# FR4_6_0.net
KiCad netlist of a schematic drawn in EAGLE
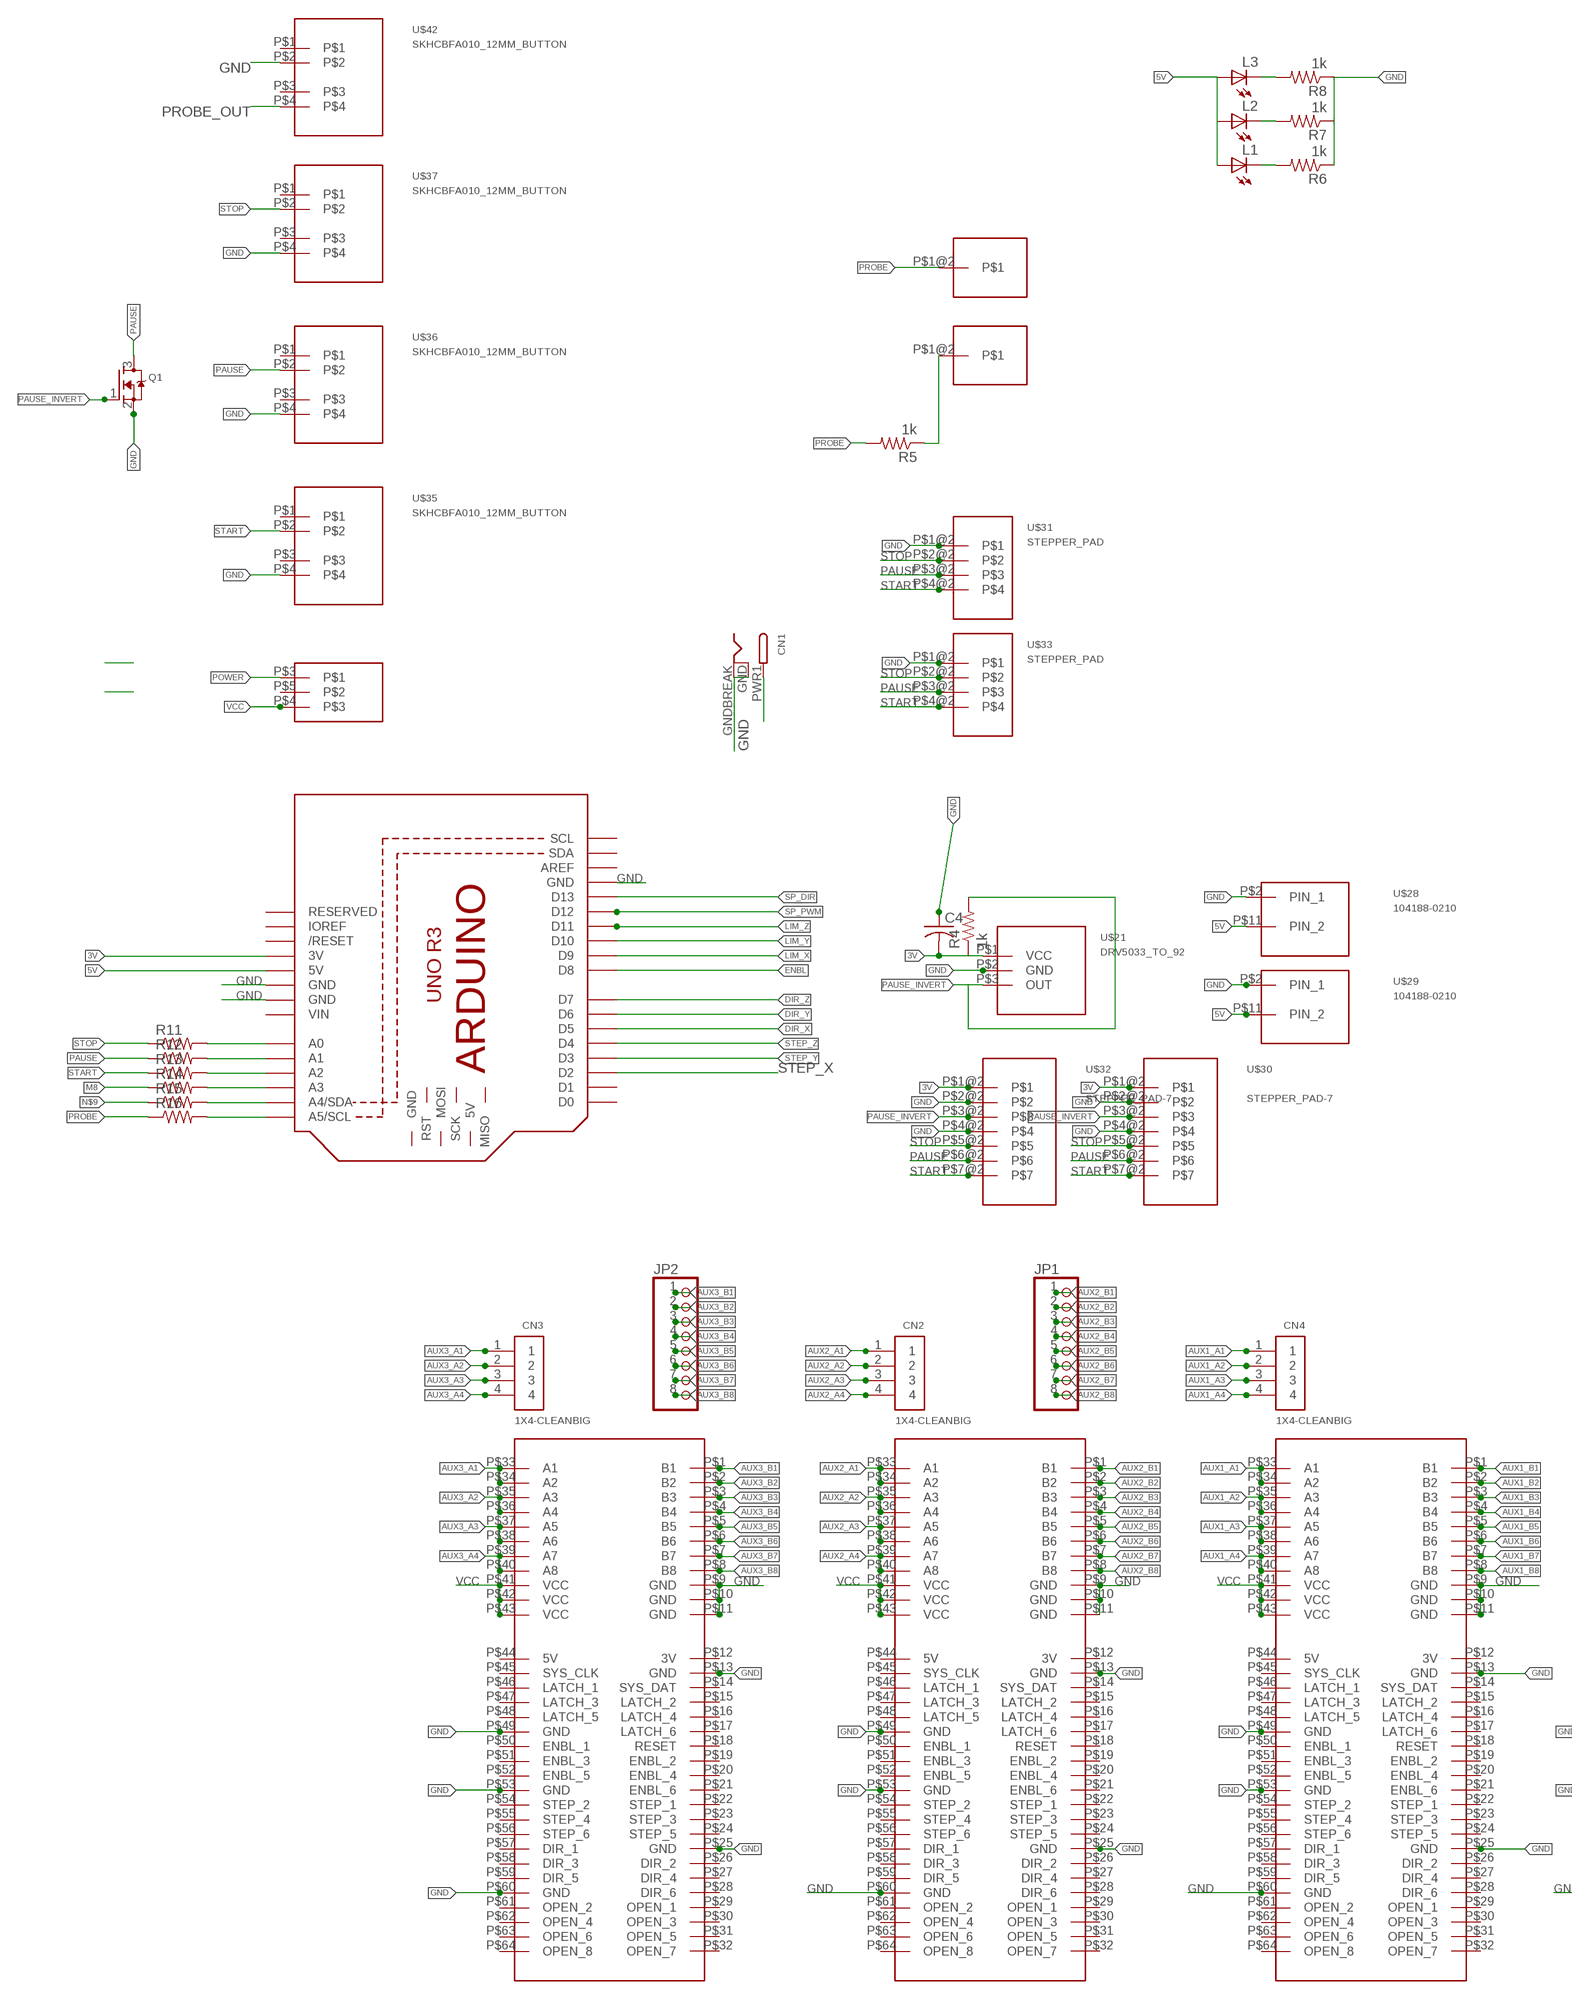
[diagram p0: schematic, sheet 1, part 1 of 2]
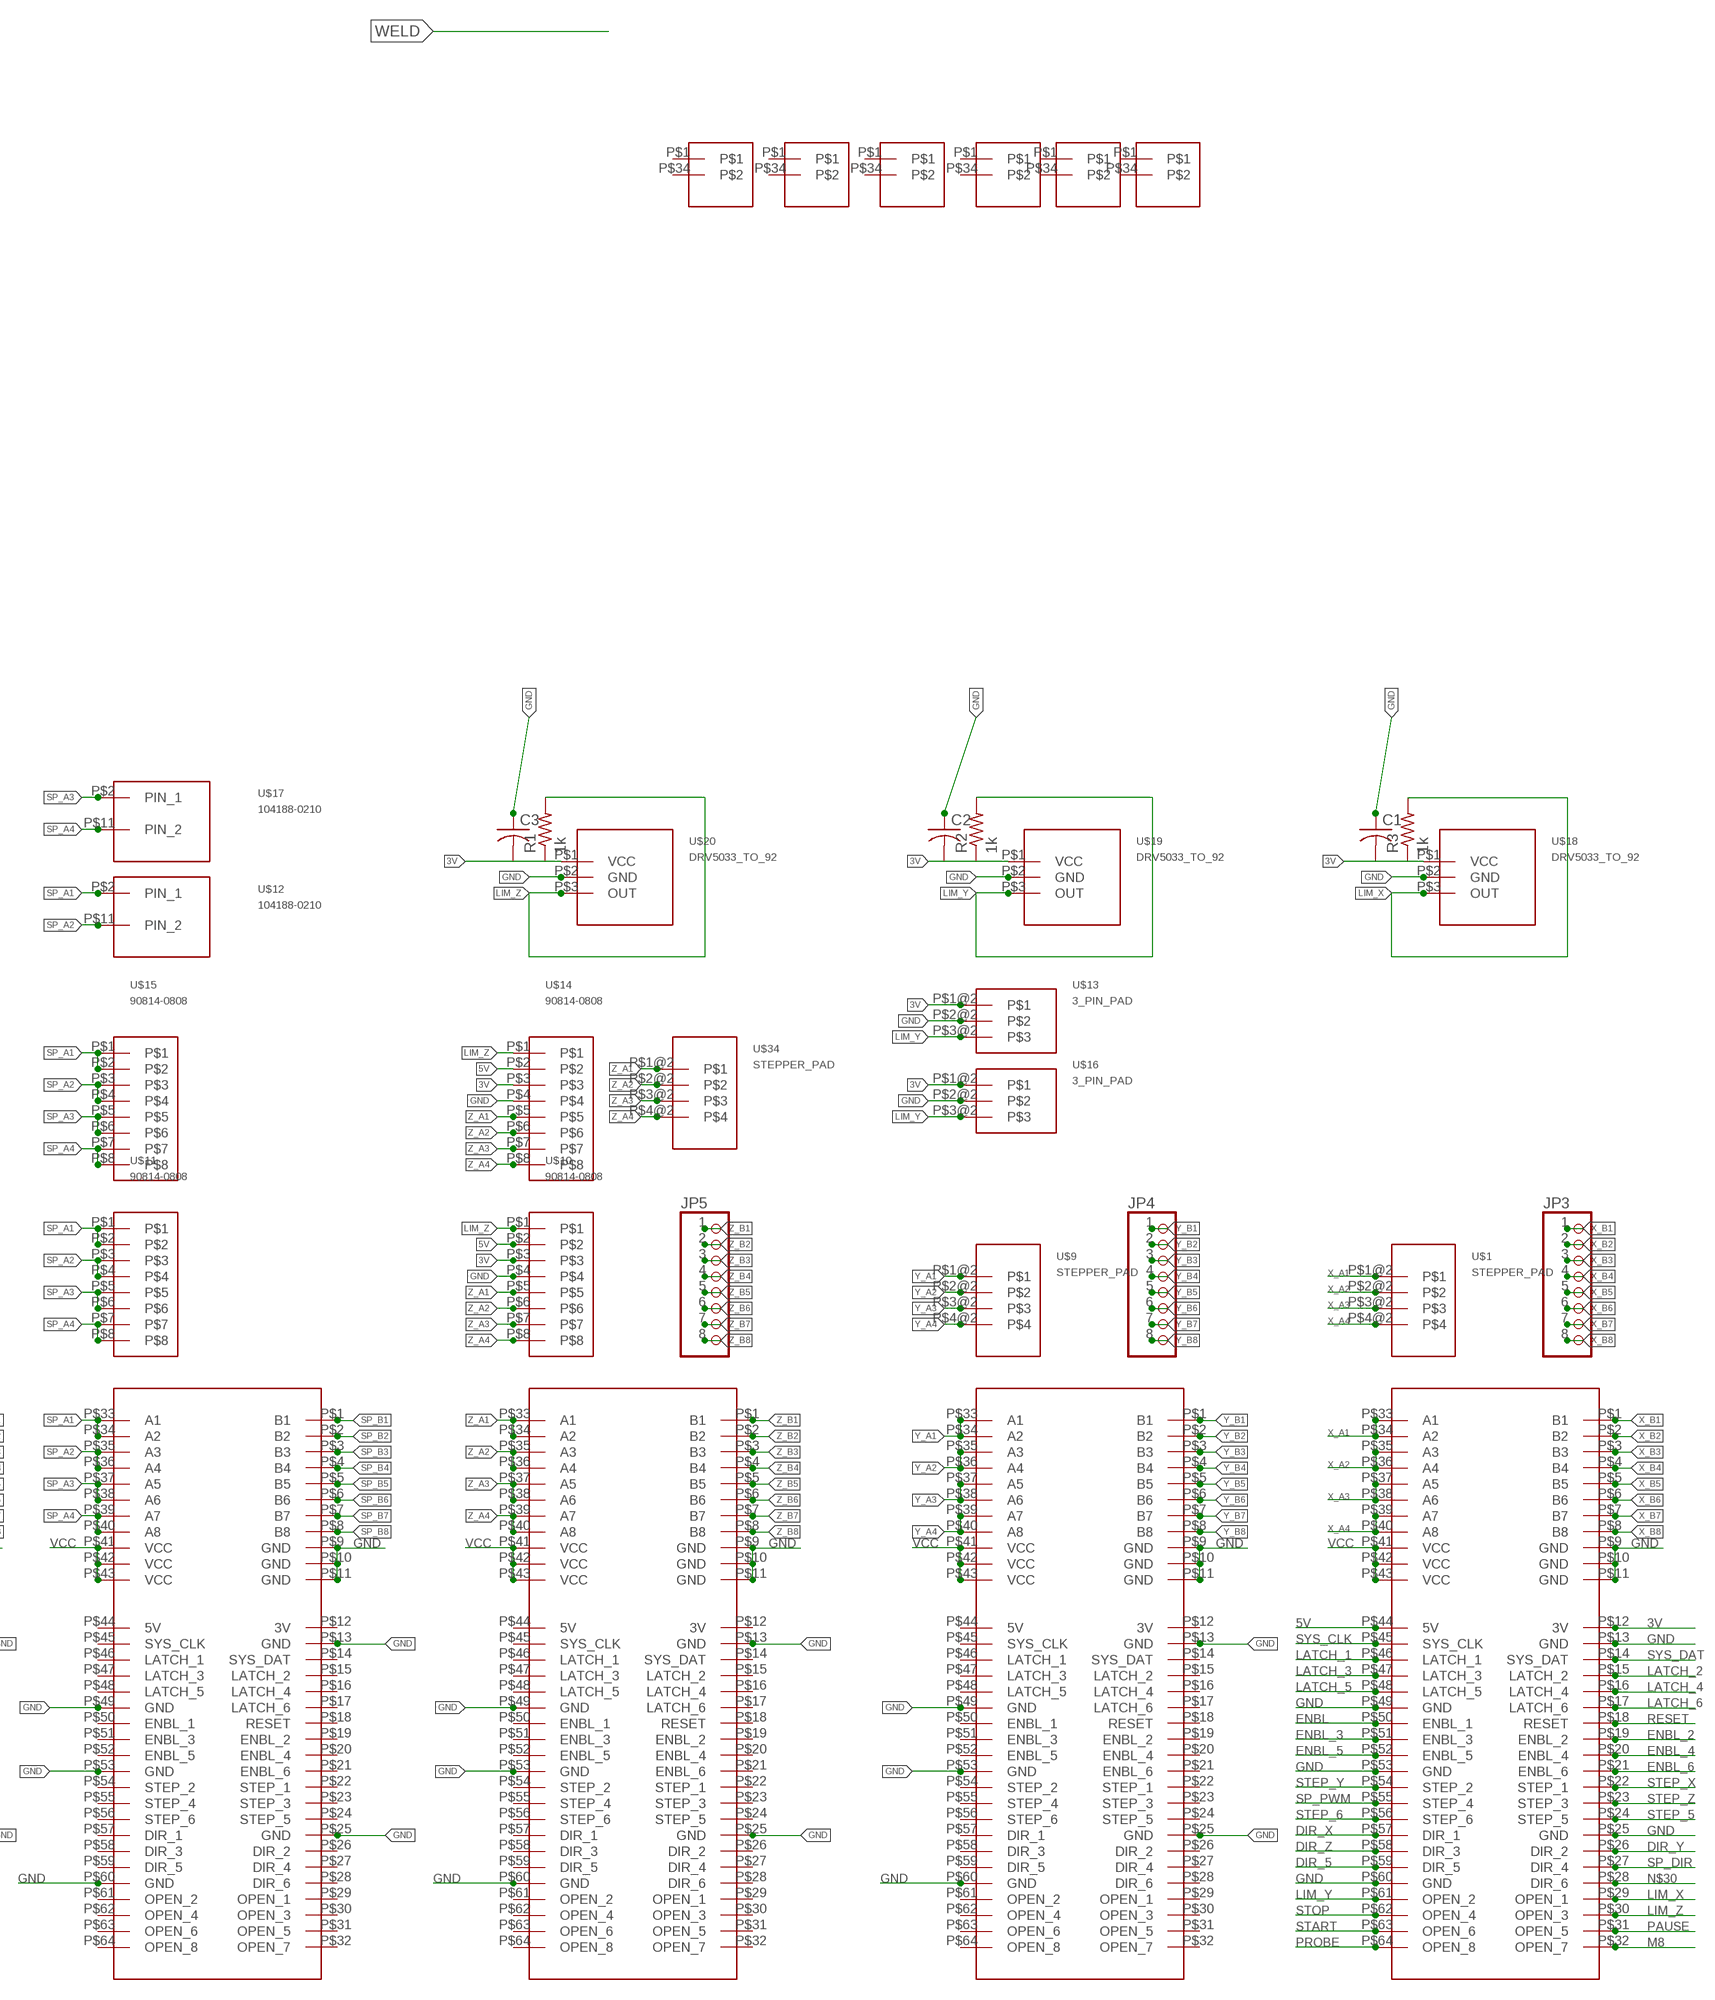
[diagram p1: schematic, sheet 1, part 2 of 2]

(export (version "E")
  (design (tool "Eeschema 10.0.6"))
  (components
    (comp (ref "C1")
      (value "C-USC1210")
      (footprint "eagle-import:C1210")
      (libsource (lib "eagle-import") (part "C-USC1210"))
    )
    (comp (ref "C2")
      (value "C-USC1210")
      (footprint "eagle-import:C1210")
      (libsource (lib "eagle-import") (part "C-USC1210"))
    )
    (comp (ref "C3")
      (value "C-USC1210")
      (footprint "eagle-import:C1210")
      (libsource (lib "eagle-import") (part "C-USC1210"))
    )
    (comp (ref "C4")
      (value "C-USC1210")
      (footprint "eagle-import:C1210")
      (libsource (lib "eagle-import") (part "C-USC1210"))
    )
    (comp (ref "CN1")
      (value "DCBARRELSMT")
      (footprint "eagle-import:DCJACK_2MM_SMT")
      (libsource (lib "eagle-import") (part "DCBARRELSMT"))
    )
    (comp (ref "CN2")
      (value "1X4-CLEANBIG")
      (footprint "eagle-import:1X04-CLEANBIG")
      (libsource (lib "eagle-import") (part "1X4-CLEANBIG"))
    )
    (comp (ref "CN3")
      (value "1X4-CLEANBIG")
      (footprint "eagle-import:1X04-CLEANBIG")
      (libsource (lib "eagle-import") (part "1X4-CLEANBIG"))
    )
    (comp (ref "CN4")
      (value "1X4-CLEANBIG")
      (footprint "eagle-import:1X04-CLEANBIG")
      (libsource (lib "eagle-import") (part "1X4-CLEANBIG"))
    )
    (comp (ref "JP1")
      (value "PINHD-1X8CLEANBIG")
      (footprint "eagle-import:1X08-CLEANBIG")
      (libsource (lib "eagle-import") (part "PINHD-1X8CLEANBIG"))
    )
    (comp (ref "JP2")
      (value "PINHD-1X8CLEANBIG")
      (footprint "eagle-import:1X08-CLEANBIG")
      (libsource (lib "eagle-import") (part "PINHD-1X8CLEANBIG"))
    )
    (comp (ref "JP3")
      (value "PINHD-1X8CLEANBIG")
      (footprint "eagle-import:1X08-CLEANBIG")
      (libsource (lib "eagle-import") (part "PINHD-1X8CLEANBIG"))
    )
    (comp (ref "JP4")
      (value "PINHD-1X8CLEANBIG")
      (footprint "eagle-import:1X08-CLEANBIG")
      (libsource (lib "eagle-import") (part "PINHD-1X8CLEANBIG"))
    )
    (comp (ref "JP5")
      (value "PINHD-1X8CLEANBIG")
      (footprint "eagle-import:1X08-CLEANBIG")
      (libsource (lib "eagle-import") (part "PINHD-1X8CLEANBIG"))
    )
    (comp (ref "L1")
      (value "LEDCHIPLED_1206")
      (footprint "eagle-import:CHIPLED_1206")
      (libsource (lib "eagle-import") (part "LEDCHIPLED_1206"))
    )
    (comp (ref "L2")
      (value "LEDCHIPLED_1206")
      (footprint "eagle-import:CHIPLED_1206")
      (libsource (lib "eagle-import") (part "LEDCHIPLED_1206"))
    )
    (comp (ref "L3")
      (value "LEDCHIPLED_1206")
      (footprint "eagle-import:CHIPLED_1206")
      (libsource (lib "eagle-import") (part "LEDCHIPLED_1206"))
    )
    (comp (ref "M1")
      (value "ARDUINO_R3_ICSP")
      (footprint "eagle-import:ARDUINOR3_ICSP")
      (libsource (lib "eagle-import") (part "ARDUINO_R3_ICSP"))
    )
    (comp (ref "Q1")
      (value "MOSFET-NREFLOW")
      (footprint "eagle-import:SOT23")
      (libsource (lib "eagle-import") (part "MOSFET-NREFLOW"))
    )
    (comp (ref "R1")
      (value "1k")
      (footprint "eagle-import:R1210")
      (libsource (lib "eagle-import") (part "R-US_R1210"))
    )
    (comp (ref "R2")
      (value "1k")
      (footprint "eagle-import:R1210")
      (libsource (lib "eagle-import") (part "R-US_R1210"))
    )
    (comp (ref "R3")
      (value "1k")
      (footprint "eagle-import:R1210")
      (libsource (lib "eagle-import") (part "R-US_R1210"))
    )
    (comp (ref "R4")
      (value "1k")
      (footprint "eagle-import:R1210")
      (libsource (lib "eagle-import") (part "R-US_R1210"))
    )
    (comp (ref "R5")
      (value "1k")
      (footprint "eagle-import:R1210")
      (libsource (lib "eagle-import") (part "R-US_R1210"))
    )
    (comp (ref "R6")
      (value "1k")
      (footprint "eagle-import:R1210")
      (libsource (lib "eagle-import") (part "R-US_R1210"))
    )
    (comp (ref "R7")
      (value "1k")
      (footprint "eagle-import:R1210")
      (libsource (lib "eagle-import") (part "R-US_R1210"))
    )
    (comp (ref "R8")
      (value "1k")
      (footprint "eagle-import:R1210")
      (libsource (lib "eagle-import") (part "R-US_R1210"))
    )
    (comp (ref "R11")
      (value "R-US_R1206")
      (footprint "eagle-import:R1206")
      (libsource (lib "eagle-import") (part "R-US_R1206"))
    )
    (comp (ref "R12")
      (value "R-US_R1206")
      (footprint "eagle-import:R1206")
      (libsource (lib "eagle-import") (part "R-US_R1206"))
    )
    (comp (ref "R13")
      (value "R-US_R1206")
      (footprint "eagle-import:R1206")
      (libsource (lib "eagle-import") (part "R-US_R1206"))
    )
    (comp (ref "R14")
      (value "R-US_R1206")
      (footprint "eagle-import:R1206")
      (libsource (lib "eagle-import") (part "R-US_R1206"))
    )
    (comp (ref "R15")
      (value "R-US_R1206")
      (footprint "eagle-import:R1206")
      (libsource (lib "eagle-import") (part "R-US_R1206"))
    )
    (comp (ref "R16")
      (value "R-US_R1206")
      (footprint "eagle-import:R1206")
      (libsource (lib "eagle-import") (part "R-US_R1206"))
    )
    (comp (ref "U$1")
      (value "STEPPER_PAD")
      (footprint "eagle-import:STEPPER_PAD")
      (libsource (lib "eagle-import") (part "STEPPER_PAD"))
    )
    (comp (ref "U$2")
      (value "10018784-10211TLF-TRACE")
      (footprint "eagle-import:10018784-10211TLF-TRACE")
      (libsource (lib "eagle-import") (part "10018784-10211TLF-TRACE"))
    )
    (comp (ref "U$3")
      (value "10018784-10211TLF-TRACE")
      (footprint "eagle-import:10018784-10211TLF-TRACE")
      (libsource (lib "eagle-import") (part "10018784-10211TLF-TRACE"))
    )
    (comp (ref "U$4")
      (value "10018784-10211TLF-TRACE")
      (footprint "eagle-import:10018784-10211TLF-TRACE")
      (libsource (lib "eagle-import") (part "10018784-10211TLF-TRACE"))
    )
    (comp (ref "U$5")
      (value "10018784-10211TLF-TRACE")
      (footprint "eagle-import:10018784-10211TLF-TRACE")
      (libsource (lib "eagle-import") (part "10018784-10211TLF-TRACE"))
    )
    (comp (ref "U$6")
      (value "10018784-10211TLF-TRACE")
      (footprint "eagle-import:10018784-10211TLF-TRACE")
      (libsource (lib "eagle-import") (part "10018784-10211TLF-TRACE"))
    )
    (comp (ref "U$7")
      (value "10018784-10211TLF-TRACE")
      (footprint "eagle-import:10018784-10211TLF-TRACE")
      (libsource (lib "eagle-import") (part "10018784-10211TLF-TRACE"))
    )
    (comp (ref "U$8")
      (value "10018784-10211TLF-")
      (footprint "eagle-import:1001874-10211TLF-")
      (libsource (lib "eagle-import") (part "10018784-10211TLF-"))
    )
    (comp (ref "U$9")
      (value "STEPPER_PAD")
      (footprint "eagle-import:STEPPER_PAD")
      (libsource (lib "eagle-import") (part "STEPPER_PAD"))
    )
    (comp (ref "U$10")
      (value "90814-0808")
      (footprint "eagle-import:90814-0808")
      (libsource (lib "eagle-import") (part "90814-0808"))
    )
    (comp (ref "U$11")
      (value "90814-0808")
      (footprint "eagle-import:90814-0808")
      (libsource (lib "eagle-import") (part "90814-0808"))
    )
    (comp (ref "U$12")
      (value "104188-0210")
      (footprint "eagle-import:104188-0210")
      (libsource (lib "eagle-import") (part "104188-0210"))
    )
    (comp (ref "U$13")
      (value "3_PIN_PAD")
      (footprint "eagle-import:3_WIRE_PAD")
      (libsource (lib "eagle-import") (part "3_PIN_PAD"))
    )
    (comp (ref "U$14")
      (value "90814-0808")
      (footprint "eagle-import:90814-0808")
      (libsource (lib "eagle-import") (part "90814-0808"))
    )
    (comp (ref "U$15")
      (value "90814-0808")
      (footprint "eagle-import:90814-0808")
      (libsource (lib "eagle-import") (part "90814-0808"))
    )
    (comp (ref "U$16")
      (value "3_PIN_PAD")
      (footprint "eagle-import:3_WIRE_PAD")
      (libsource (lib "eagle-import") (part "3_PIN_PAD"))
    )
    (comp (ref "U$17")
      (value "104188-0210")
      (footprint "eagle-import:104188-0210")
      (libsource (lib "eagle-import") (part "104188-0210"))
    )
    (comp (ref "U$18")
      (value "DRV5033_TO_92")
      (footprint "eagle-import:DRV5033_TO_92")
      (libsource (lib "eagle-import") (part "DRV5033_TO_92"))
    )
    (comp (ref "U$19")
      (value "DRV5033_TO_92")
      (footprint "eagle-import:DRV5033_TO_92")
      (libsource (lib "eagle-import") (part "DRV5033_TO_92"))
    )
    (comp (ref "U$20")
      (value "DRV5033_TO_92")
      (footprint "eagle-import:DRV5033_TO_92")
      (libsource (lib "eagle-import") (part "DRV5033_TO_92"))
    )
    (comp (ref "U$21")
      (value "DRV5033_TO_92")
      (footprint "eagle-import:DRV5033_TO_92")
      (libsource (lib "eagle-import") (part "DRV5033_TO_92"))
    )
    (comp (ref "U$22")
      (value "WELDPAD_.79X.353")
      (footprint "eagle-import:WELDPAD_.79X.353")
      (libsource (lib "eagle-import") (part "WELDPAD_.79X.353"))
    )
    (comp (ref "U$23")
      (value "WELDPAD_.79X.353")
      (footprint "eagle-import:WELDPAD_.79X.353")
      (libsource (lib "eagle-import") (part "WELDPAD_.79X.353"))
    )
    (comp (ref "U$24")
      (value "WELDPAD_.79X.353")
      (footprint "eagle-import:WELDPAD_.79X.353")
      (libsource (lib "eagle-import") (part "WELDPAD_.79X.353"))
    )
    (comp (ref "U$25")
      (value "WELDPAD_.79X.353")
      (footprint "eagle-import:WELDPAD_.79X.353")
      (libsource (lib "eagle-import") (part "WELDPAD_.79X.353"))
    )
    (comp (ref "U$26")
      (value "WELDPAD_.79X.353")
      (footprint "eagle-import:WELDPAD_.79X.353")
      (libsource (lib "eagle-import") (part "WELDPAD_.79X.353"))
    )
    (comp (ref "U$27")
      (value "WELDPAD_.79X.353")
      (footprint "eagle-import:WELDPAD_.79X.353")
      (libsource (lib "eagle-import") (part "WELDPAD_.79X.353"))
    )
    (comp (ref "U$28")
      (value "104188-0210")
      (footprint "eagle-import:104188-0210")
      (libsource (lib "eagle-import") (part "104188-0210"))
    )
    (comp (ref "U$29")
      (value "104188-0210")
      (footprint "eagle-import:104188-0210")
      (libsource (lib "eagle-import") (part "104188-0210"))
    )
    (comp (ref "U$30")
      (value "STEPPER_PAD-7")
      (footprint "eagle-import:STEPPER_PAD-7")
      (libsource (lib "eagle-import") (part "STEPPER_PAD-7"))
    )
    (comp (ref "U$31")
      (value "STEPPER_PAD")
      (footprint "eagle-import:STEPPER_PAD")
      (libsource (lib "eagle-import") (part "STEPPER_PAD"))
    )
    (comp (ref "U$32")
      (value "STEPPER_PAD-7")
      (footprint "eagle-import:STEPPER_PAD-7")
      (libsource (lib "eagle-import") (part "STEPPER_PAD-7"))
    )
    (comp (ref "U$33")
      (value "STEPPER_PAD")
      (footprint "eagle-import:STEPPER_PAD")
      (libsource (lib "eagle-import") (part "STEPPER_PAD"))
    )
    (comp (ref "U$34")
      (value "STEPPER_PAD")
      (footprint "eagle-import:STEPPER_PAD")
      (libsource (lib "eagle-import") (part "STEPPER_PAD"))
    )
    (comp (ref "U$35")
      (value "SKHCBFA010_12MM_BUTTON")
      (footprint "eagle-import:12MM_BUTTON")
      (libsource (lib "eagle-import") (part "SKHCBFA010_12MM_BUTTON"))
    )
    (comp (ref "U$36")
      (value "SKHCBFA010_12MM_BUTTON")
      (footprint "eagle-import:12MM_BUTTON")
      (libsource (lib "eagle-import") (part "SKHCBFA010_12MM_BUTTON"))
    )
    (comp (ref "U$37")
      (value "SKHCBFA010_12MM_BUTTON")
      (footprint "eagle-import:12MM_BUTTON")
      (libsource (lib "eagle-import") (part "SKHCBFA010_12MM_BUTTON"))
    )
    (comp (ref "U$39")
      (value "1PIN_PAD")
      (footprint "eagle-import:1PIN_PAD")
      (libsource (lib "eagle-import") (part "1PIN_PAD"))
    )
    (comp (ref "U$40")
      (value "1PIN_PAD")
      (footprint "eagle-import:1PIN_PAD")
      (libsource (lib "eagle-import") (part "1PIN_PAD"))
    )
    (comp (ref "U$41")
      (value "100SP1T2B4M6QE")
      (footprint "eagle-import:100SP1T2B4M6QE")
      (libsource (lib "eagle-import") (part "100SP1T2B4M6QE"))
    )
    (comp (ref "U$42")
      (value "SKHCBFA010_12MM_BUTTON")
      (footprint "eagle-import:12MM_BUTTON")
      (libsource (lib "eagle-import") (part "SKHCBFA010_12MM_BUTTON"))
    )
  )
  (nets
    (net (code "1") (name "/DIR_5") (class "Default")
      (node (ref "U$8") (pin "P$59") (pinfunction "DIR_5_P$59") (pintype "bidirectional"))
    )
    (net (code "2") (name "/ENBL_2") (class "Default")
      (node (ref "U$8") (pin "P$19") (pinfunction "ENBL_2_P$19") (pintype "bidirectional"))
    )
    (net (code "3") (name "/ENBL_3") (class "Default")
      (node (ref "U$8") (pin "P$51") (pinfunction "ENBL_3_P$51") (pintype "bidirectional"))
    )
    (net (code "4") (name "/ENBL_4") (class "Default")
      (node (ref "U$8") (pin "P$20") (pinfunction "ENBL_4_P$20") (pintype "bidirectional"))
    )
    (net (code "5") (name "/ENBL_5") (class "Default")
      (node (ref "U$8") (pin "P$52") (pinfunction "ENBL_5_P$52") (pintype "bidirectional"))
    )
    (net (code "6") (name "/ENBL_6") (class "Default")
      (node (ref "U$8") (pin "P$21") (pinfunction "ENBL_6_P$21") (pintype "bidirectional"))
    )
    (net (code "7") (name "/LATCH_1") (class "Default")
      (node (ref "U$8") (pin "P$46") (pinfunction "LATCH_1_P$46") (pintype "bidirectional"))
    )
    (net (code "8") (name "/LATCH_2") (class "Default")
      (node (ref "U$8") (pin "P$15") (pinfunction "LATCH_2_P$15") (pintype "bidirectional"))
    )
    (net (code "9") (name "/LATCH_3") (class "Default")
      (node (ref "U$8") (pin "P$47") (pinfunction "LATCH_3_P$47") (pintype "bidirectional"))
    )
    (net (code "10") (name "/LATCH_4") (class "Default")
      (node (ref "U$8") (pin "P$16") (pinfunction "LATCH_4_P$16") (pintype "bidirectional"))
    )
    (net (code "11") (name "/LATCH_5") (class "Default")
      (node (ref "U$8") (pin "P$48") (pinfunction "LATCH_5_P$48") (pintype "bidirectional"))
    )
    (net (code "12") (name "/LATCH_6") (class "Default")
      (node (ref "U$8") (pin "P$17") (pinfunction "LATCH_6_P$17") (pintype "bidirectional"))
    )
    (net (code "13") (name "/N$30") (class "Default")
      (node (ref "U$8") (pin "P$28") (pinfunction "DIR_6_P$28") (pintype "bidirectional"))
    )
    (net (code "14") (name "/PROBE_OUT") (class "Default")
      (node (ref "R5") (pin "1") (pinfunction "1_1") (pintype "passive"))
      (node (ref "U$39") (pin "P$1@2") (pinfunction "P$1_P$1@2") (pintype "bidirectional"))
      (node (ref "U$42") (pin "P$4") (pinfunction "P$4_P$4") (pintype "bidirectional"))
    )
    (net (code "15") (name "/RESET") (class "Default")
      (node (ref "U$8") (pin "P$18") (pinfunction "RESET_P$18") (pintype "bidirectional"))
    )
    (net (code "16") (name "/STEP_5") (class "Default")
      (node (ref "U$8") (pin "P$24") (pinfunction "STEP_5_P$24") (pintype "bidirectional"))
    )
    (net (code "17") (name "/STEP_6") (class "Default")
      (node (ref "U$8") (pin "P$56") (pinfunction "STEP_6_P$56") (pintype "bidirectional"))
    )
    (net (code "18") (name "/STEP_X") (class "Default")
      (node (ref "M1") (pin "D2") (pinfunction "D2_D2") (pintype "bidirectional"))
      (node (ref "U$8") (pin "P$22") (pinfunction "STEP_1_P$22") (pintype "bidirectional"))
    )
    (net (code "19") (name "/SYS_CLK") (class "Default")
      (node (ref "U$8") (pin "P$45") (pinfunction "SYS_CLK_P$45") (pintype "bidirectional"))
    )
    (net (code "20") (name "/SYS_DAT") (class "Default")
      (node (ref "U$8") (pin "P$14") (pinfunction "SYS_DAT_P$14") (pintype "bidirectional"))
    )
    (net (code "21") (name "/VIN") (class "Default")
      (node (ref "M1") (pin "VIN") (pinfunction "VIN_VIN") (pintype "power_in"))
    )
    (net (code "22") (name "/X_A1") (class "Default")
      (node (ref "U$1") (pin "P$1@2") (pinfunction "P$1_P$1@2") (pintype "bidirectional"))
      (node (ref "U$8") (pin "P$33") (pinfunction "A1_P$33") (pintype "bidirectional"))
      (node (ref "U$8") (pin "P$34") (pinfunction "A2_P$34") (pintype "bidirectional"))
    )
    (net (code "23") (name "/X_A2") (class "Default")
      (node (ref "U$1") (pin "P$2@2") (pinfunction "P$2_P$2@2") (pintype "bidirectional"))
      (node (ref "U$8") (pin "P$35") (pinfunction "A3_P$35") (pintype "bidirectional"))
      (node (ref "U$8") (pin "P$36") (pinfunction "A4_P$36") (pintype "bidirectional"))
    )
    (net (code "24") (name "/X_A3") (class "Default")
      (node (ref "U$1") (pin "P$3@2") (pinfunction "P$3_P$3@2") (pintype "bidirectional"))
      (node (ref "U$8") (pin "P$37") (pinfunction "A5_P$37") (pintype "bidirectional"))
      (node (ref "U$8") (pin "P$38") (pinfunction "A6_P$38") (pintype "bidirectional"))
    )
    (net (code "25") (name "/X_A4") (class "Default")
      (node (ref "U$1") (pin "P$4@2") (pinfunction "P$4_P$4@2") (pintype "bidirectional"))
      (node (ref "U$8") (pin "P$39") (pinfunction "A7_P$39") (pintype "bidirectional"))
      (node (ref "U$8") (pin "P$40") (pinfunction "A8_P$40") (pintype "bidirectional"))
    )
    (net (code "26") (name "3V") (class "Default")
      (node (ref "C1") (pin "2") (pinfunction "2_2") (pintype "passive"))
      (node (ref "C2") (pin "2") (pinfunction "2_2") (pintype "passive"))
      (node (ref "C3") (pin "2") (pinfunction "2_2") (pintype "passive"))
      (node (ref "C4") (pin "2") (pinfunction "2_2") (pintype "passive"))
      (node (ref "M1") (pin "3V") (pinfunction "3V_3V") (pintype "power_in"))
      (node (ref "R1") (pin "1") (pinfunction "1_1") (pintype "passive"))
      (node (ref "R2") (pin "1") (pinfunction "1_1") (pintype "passive"))
      (node (ref "R3") (pin "1") (pinfunction "1_1") (pintype "passive"))
      (node (ref "R4") (pin "1") (pinfunction "1_1") (pintype "passive"))
      (node (ref "U$10") (pin "P$3") (pinfunction "P$3_P$3") (pintype "bidirectional"))
      (node (ref "U$13") (pin "P$1@2") (pinfunction "P$1_P$1@2") (pintype "bidirectional"))
      (node (ref "U$14") (pin "P$3") (pinfunction "P$3_P$3") (pintype "bidirectional"))
      (node (ref "U$16") (pin "P$1@2") (pinfunction "P$1_P$1@2") (pintype "bidirectional"))
      (node (ref "U$18") (pin "P$1") (pinfunction "VCC_P$1") (pintype "bidirectional"))
      (node (ref "U$19") (pin "P$1") (pinfunction "VCC_P$1") (pintype "bidirectional"))
      (node (ref "U$20") (pin "P$1") (pinfunction "VCC_P$1") (pintype "bidirectional"))
      (node (ref "U$21") (pin "P$1") (pinfunction "VCC_P$1") (pintype "bidirectional"))
      (node (ref "U$30") (pin "P$1@2") (pinfunction "P$1_P$1@2") (pintype "bidirectional"))
      (node (ref "U$32") (pin "P$1@2") (pinfunction "P$1_P$1@2") (pintype "bidirectional"))
      (node (ref "U$8") (pin "P$12") (pinfunction "3V_P$12") (pintype "bidirectional"))
    )
    (net (code "27") (name "5V") (class "Default")
      (node (ref "L1") (pin "A") (pinfunction "A_A") (pintype "passive"))
      (node (ref "L2") (pin "A") (pinfunction "A_A") (pintype "passive"))
      (node (ref "L3") (pin "A") (pinfunction "A_A") (pintype "passive"))
      (node (ref "M1") (pin "5V") (pinfunction "5V_5V") (pintype "power_in"))
      (node (ref "U$10") (pin "P$2") (pinfunction "P$2_P$2") (pintype "bidirectional"))
      (node (ref "U$14") (pin "P$2") (pinfunction "P$2_P$2") (pintype "bidirectional"))
      (node (ref "U$28") (pin "P$11") (pinfunction "PIN_2_P$11") (pintype "bidirectional"))
      (node (ref "U$29") (pin "P$11") (pinfunction "PIN_2_P$11") (pintype "bidirectional"))
      (node (ref "U$8") (pin "P$44") (pinfunction "5V_P$44") (pintype "bidirectional"))
    )
    (net (code "28") (name "AUX1_A1") (class "Default")
      (node (ref "CN4") (pin "1") (pinfunction "1_1") (pintype "bidirectional"))
      (node (ref "U$4") (pin "P$33") (pinfunction "A1_P$33") (pintype "bidirectional"))
      (node (ref "U$4") (pin "P$34") (pinfunction "A2_P$34") (pintype "bidirectional"))
    )
    (net (code "29") (name "AUX1_A2") (class "Default")
      (node (ref "CN4") (pin "2") (pinfunction "2_2") (pintype "bidirectional"))
      (node (ref "U$4") (pin "P$35") (pinfunction "A3_P$35") (pintype "bidirectional"))
      (node (ref "U$4") (pin "P$36") (pinfunction "A4_P$36") (pintype "bidirectional"))
    )
    (net (code "30") (name "AUX1_A3") (class "Default")
      (node (ref "CN4") (pin "3") (pinfunction "3_3") (pintype "bidirectional"))
      (node (ref "U$4") (pin "P$37") (pinfunction "A5_P$37") (pintype "bidirectional"))
      (node (ref "U$4") (pin "P$38") (pinfunction "A6_P$38") (pintype "bidirectional"))
    )
    (net (code "31") (name "AUX1_A4") (class "Default")
      (node (ref "CN4") (pin "4") (pinfunction "4_4") (pintype "bidirectional"))
      (node (ref "U$4") (pin "P$39") (pinfunction "A7_P$39") (pintype "bidirectional"))
      (node (ref "U$4") (pin "P$40") (pinfunction "A8_P$40") (pintype "bidirectional"))
    )
    (net (code "32") (name "AUX1_B1") (class "Default")
      (node (ref "U$4") (pin "P$1") (pinfunction "B1_P$1") (pintype "bidirectional"))
    )
    (net (code "33") (name "AUX1_B2") (class "Default")
      (node (ref "U$4") (pin "P$2") (pinfunction "B2_P$2") (pintype "bidirectional"))
    )
    (net (code "34") (name "AUX1_B3") (class "Default")
      (node (ref "U$4") (pin "P$3") (pinfunction "B3_P$3") (pintype "bidirectional"))
    )
    (net (code "35") (name "AUX1_B4") (class "Default")
      (node (ref "U$4") (pin "P$4") (pinfunction "B4_P$4") (pintype "bidirectional"))
    )
    (net (code "36") (name "AUX1_B5") (class "Default")
      (node (ref "U$4") (pin "P$5") (pinfunction "B5_P$5") (pintype "bidirectional"))
    )
    (net (code "37") (name "AUX1_B6") (class "Default")
      (node (ref "U$4") (pin "P$6") (pinfunction "B6_P$6") (pintype "bidirectional"))
    )
    (net (code "38") (name "AUX1_B7") (class "Default")
      (node (ref "U$4") (pin "P$7") (pinfunction "B7_P$7") (pintype "bidirectional"))
    )
    (net (code "39") (name "AUX1_B8") (class "Default")
      (node (ref "U$4") (pin "P$8") (pinfunction "B8_P$8") (pintype "bidirectional"))
    )
    (net (code "40") (name "AUX2_A1") (class "Default")
      (node (ref "CN2") (pin "1") (pinfunction "1_1") (pintype "bidirectional"))
      (node (ref "U$3") (pin "P$33") (pinfunction "A1_P$33") (pintype "bidirectional"))
      (node (ref "U$3") (pin "P$34") (pinfunction "A2_P$34") (pintype "bidirectional"))
    )
    (net (code "41") (name "AUX2_A2") (class "Default")
      (node (ref "CN2") (pin "2") (pinfunction "2_2") (pintype "bidirectional"))
      (node (ref "U$3") (pin "P$35") (pinfunction "A3_P$35") (pintype "bidirectional"))
      (node (ref "U$3") (pin "P$36") (pinfunction "A4_P$36") (pintype "bidirectional"))
    )
    (net (code "42") (name "AUX2_A3") (class "Default")
      (node (ref "CN2") (pin "3") (pinfunction "3_3") (pintype "bidirectional"))
      (node (ref "U$3") (pin "P$37") (pinfunction "A5_P$37") (pintype "bidirectional"))
      (node (ref "U$3") (pin "P$38") (pinfunction "A6_P$38") (pintype "bidirectional"))
    )
    (net (code "43") (name "AUX2_A4") (class "Default")
      (node (ref "CN2") (pin "4") (pinfunction "4_4") (pintype "bidirectional"))
      (node (ref "U$3") (pin "P$39") (pinfunction "A7_P$39") (pintype "bidirectional"))
      (node (ref "U$3") (pin "P$40") (pinfunction "A8_P$40") (pintype "bidirectional"))
    )
    (net (code "44") (name "AUX2_B1") (class "Default")
      (node (ref "JP1") (pin "1") (pinfunction "1_1") (pintype "passive"))
      (node (ref "U$3") (pin "P$1") (pinfunction "B1_P$1") (pintype "bidirectional"))
    )
    (net (code "45") (name "AUX2_B2") (class "Default")
      (node (ref "JP1") (pin "2") (pinfunction "2_2") (pintype "passive"))
      (node (ref "U$3") (pin "P$2") (pinfunction "B2_P$2") (pintype "bidirectional"))
    )
    (net (code "46") (name "AUX2_B3") (class "Default")
      (node (ref "JP1") (pin "3") (pinfunction "3_3") (pintype "passive"))
      (node (ref "U$3") (pin "P$3") (pinfunction "B3_P$3") (pintype "bidirectional"))
    )
    (net (code "47") (name "AUX2_B4") (class "Default")
      (node (ref "JP1") (pin "4") (pinfunction "4_4") (pintype "passive"))
      (node (ref "U$3") (pin "P$4") (pinfunction "B4_P$4") (pintype "bidirectional"))
    )
    (net (code "48") (name "AUX2_B5") (class "Default")
      (node (ref "JP1") (pin "5") (pinfunction "5_5") (pintype "passive"))
      (node (ref "U$3") (pin "P$5") (pinfunction "B5_P$5") (pintype "bidirectional"))
    )
    (net (code "49") (name "AUX2_B6") (class "Default")
      (node (ref "JP1") (pin "6") (pinfunction "6_6") (pintype "passive"))
      (node (ref "U$3") (pin "P$6") (pinfunction "B6_P$6") (pintype "bidirectional"))
    )
    (net (code "50") (name "AUX2_B7") (class "Default")
      (node (ref "JP1") (pin "7") (pinfunction "7_7") (pintype "passive"))
      (node (ref "U$3") (pin "P$7") (pinfunction "B7_P$7") (pintype "bidirectional"))
    )
    (net (code "51") (name "AUX2_B8") (class "Default")
      (node (ref "JP1") (pin "8") (pinfunction "8_8") (pintype "passive"))
      (node (ref "U$3") (pin "P$8") (pinfunction "B8_P$8") (pintype "bidirectional"))
    )
    (net (code "52") (name "AUX3_A1") (class "Default")
      (node (ref "CN3") (pin "1") (pinfunction "1_1") (pintype "bidirectional"))
      (node (ref "U$2") (pin "P$33") (pinfunction "A1_P$33") (pintype "bidirectional"))
      (node (ref "U$2") (pin "P$34") (pinfunction "A2_P$34") (pintype "bidirectional"))
    )
    (net (code "53") (name "AUX3_A2") (class "Default")
      (node (ref "CN3") (pin "2") (pinfunction "2_2") (pintype "bidirectional"))
      (node (ref "U$2") (pin "P$35") (pinfunction "A3_P$35") (pintype "bidirectional"))
      (node (ref "U$2") (pin "P$36") (pinfunction "A4_P$36") (pintype "bidirectional"))
    )
    (net (code "54") (name "AUX3_A3") (class "Default")
      (node (ref "CN3") (pin "3") (pinfunction "3_3") (pintype "bidirectional"))
      (node (ref "U$2") (pin "P$37") (pinfunction "A5_P$37") (pintype "bidirectional"))
      (node (ref "U$2") (pin "P$38") (pinfunction "A6_P$38") (pintype "bidirectional"))
    )
    (net (code "55") (name "AUX3_A4") (class "Default")
      (node (ref "CN3") (pin "4") (pinfunction "4_4") (pintype "bidirectional"))
      (node (ref "U$2") (pin "P$39") (pinfunction "A7_P$39") (pintype "bidirectional"))
      (node (ref "U$2") (pin "P$40") (pinfunction "A8_P$40") (pintype "bidirectional"))
    )
    (net (code "56") (name "AUX3_B1") (class "Default")
      (node (ref "JP2") (pin "1") (pinfunction "1_1") (pintype "passive"))
      (node (ref "U$2") (pin "P$1") (pinfunction "B1_P$1") (pintype "bidirectional"))
    )
    (net (code "57") (name "AUX3_B2") (class "Default")
      (node (ref "JP2") (pin "2") (pinfunction "2_2") (pintype "passive"))
      (node (ref "U$2") (pin "P$2") (pinfunction "B2_P$2") (pintype "bidirectional"))
    )
    (net (code "58") (name "AUX3_B3") (class "Default")
      (node (ref "JP2") (pin "3") (pinfunction "3_3") (pintype "passive"))
      (node (ref "U$2") (pin "P$3") (pinfunction "B3_P$3") (pintype "bidirectional"))
    )
    (net (code "59") (name "AUX3_B4") (class "Default")
      (node (ref "JP2") (pin "4") (pinfunction "4_4") (pintype "passive"))
      (node (ref "U$2") (pin "P$4") (pinfunction "B4_P$4") (pintype "bidirectional"))
    )
    (net (code "60") (name "AUX3_B5") (class "Default")
      (node (ref "JP2") (pin "5") (pinfunction "5_5") (pintype "passive"))
      (node (ref "U$2") (pin "P$5") (pinfunction "B5_P$5") (pintype "bidirectional"))
    )
    (net (code "61") (name "AUX3_B6") (class "Default")
      (node (ref "JP2") (pin "6") (pinfunction "6_6") (pintype "passive"))
      (node (ref "U$2") (pin "P$6") (pinfunction "B6_P$6") (pintype "bidirectional"))
    )
    (net (code "62") (name "AUX3_B7") (class "Default")
      (node (ref "JP2") (pin "7") (pinfunction "7_7") (pintype "passive"))
      (node (ref "U$2") (pin "P$7") (pinfunction "B7_P$7") (pintype "bidirectional"))
    )
    (net (code "63") (name "AUX3_B8") (class "Default")
      (node (ref "JP2") (pin "8") (pinfunction "8_8") (pintype "passive"))
      (node (ref "U$2") (pin "P$8") (pinfunction "B8_P$8") (pintype "bidirectional"))
    )
    (net (code "64") (name "DIR_X") (class "Default")
      (node (ref "M1") (pin "D5") (pinfunction "D5_D5") (pintype "bidirectional"))
      (node (ref "U$8") (pin "P$57") (pinfunction "DIR_1_P$57") (pintype "bidirectional"))
    )
    (net (code "65") (name "DIR_Y") (class "Default")
      (node (ref "M1") (pin "D6") (pinfunction "D6_D6") (pintype "bidirectional"))
      (node (ref "U$8") (pin "P$26") (pinfunction "DIR_2_P$26") (pintype "bidirectional"))
    )
    (net (code "66") (name "DIR_Z") (class "Default")
      (node (ref "M1") (pin "D7") (pinfunction "D7_D7") (pintype "bidirectional"))
      (node (ref "U$8") (pin "P$58") (pinfunction "DIR_3_P$58") (pintype "bidirectional"))
    )
    (net (code "67") (name "ENBL") (class "Default")
      (node (ref "M1") (pin "D8") (pinfunction "D8_D8") (pintype "bidirectional"))
      (node (ref "U$8") (pin "P$50") (pinfunction "ENBL_1_P$50") (pintype "bidirectional"))
    )
    (net (code "68") (name "GND") (class "Default")
      (node (ref "C1") (pin "1") (pinfunction "1_1") (pintype "passive"))
      (node (ref "C2") (pin "1") (pinfunction "1_1") (pintype "passive"))
      (node (ref "C3") (pin "1") (pinfunction "1_1") (pintype "passive"))
      (node (ref "C4") (pin "1") (pinfunction "1_1") (pintype "passive"))
      (node (ref "CN1") (pin "GND") (pinfunction "GNDBREAK_GND") (pintype "power_in"))
      (node (ref "CN1") (pin "GNDBREAK") (pinfunction "GND_GNDBREAK") (pintype "power_in"))
      (node (ref "M1") (pin "GND") (pinfunction "GND_GND") (pintype "power_in"))
      (node (ref "M1") (pin "GND@1") (pinfunction "GND_GND@1") (pintype "power_in"))
      (node (ref "M1") (pin "GND@3") (pinfunction "GND_GND@3") (pintype "power_in"))
      (node (ref "Q1") (pin "2") (pinfunction "S_2") (pintype "bidirectional"))
      (node (ref "R6") (pin "1") (pinfunction "1_1") (pintype "passive"))
      (node (ref "R7") (pin "1") (pinfunction "1_1") (pintype "passive"))
      (node (ref "R8") (pin "1") (pinfunction "1_1") (pintype "passive"))
      (node (ref "U$10") (pin "P$4") (pinfunction "P$4_P$4") (pintype "bidirectional"))
      (node (ref "U$13") (pin "P$2@2") (pinfunction "P$2_P$2@2") (pintype "bidirectional"))
      (node (ref "U$14") (pin "P$4") (pinfunction "P$4_P$4") (pintype "bidirectional"))
      (node (ref "U$16") (pin "P$2@2") (pinfunction "P$2_P$2@2") (pintype "bidirectional"))
      (node (ref "U$18") (pin "P$2") (pinfunction "GND_P$2") (pintype "bidirectional"))
      (node (ref "U$19") (pin "P$2") (pinfunction "GND_P$2") (pintype "bidirectional"))
      (node (ref "U$2") (pin "P$10") (pinfunction "GND_P$10") (pintype "bidirectional"))
      (node (ref "U$2") (pin "P$11") (pinfunction "GND_P$11") (pintype "bidirectional"))
      (node (ref "U$2") (pin "P$13") (pinfunction "GND_P$13") (pintype "bidirectional"))
      (node (ref "U$2") (pin "P$25") (pinfunction "GND_P$25") (pintype "bidirectional"))
      (node (ref "U$2") (pin "P$49") (pinfunction "GND_P$49") (pintype "bidirectional"))
      (node (ref "U$2") (pin "P$53") (pinfunction "GND_P$53") (pintype "bidirectional"))
      (node (ref "U$2") (pin "P$60") (pinfunction "GND_P$60") (pintype "bidirectional"))
      (node (ref "U$2") (pin "P$9") (pinfunction "GND_P$9") (pintype "bidirectional"))
      (node (ref "U$20") (pin "P$2") (pinfunction "GND_P$2") (pintype "bidirectional"))
      (node (ref "U$21") (pin "P$2") (pinfunction "GND_P$2") (pintype "bidirectional"))
      (node (ref "U$28") (pin "P$2") (pinfunction "PIN_1_P$2") (pintype "bidirectional"))
      (node (ref "U$29") (pin "P$2") (pinfunction "PIN_1_P$2") (pintype "bidirectional"))
      (node (ref "U$3") (pin "P$10") (pinfunction "GND_P$10") (pintype "bidirectional"))
      (node (ref "U$3") (pin "P$11") (pinfunction "GND_P$11") (pintype "bidirectional"))
      (node (ref "U$3") (pin "P$13") (pinfunction "GND_P$13") (pintype "bidirectional"))
      (node (ref "U$3") (pin "P$25") (pinfunction "GND_P$25") (pintype "bidirectional"))
      (node (ref "U$3") (pin "P$49") (pinfunction "GND_P$49") (pintype "bidirectional"))
      (node (ref "U$3") (pin "P$53") (pinfunction "GND_P$53") (pintype "bidirectional"))
      (node (ref "U$3") (pin "P$60") (pinfunction "GND_P$60") (pintype "bidirectional"))
      (node (ref "U$3") (pin "P$9") (pinfunction "GND_P$9") (pintype "bidirectional"))
      (node (ref "U$30") (pin "P$2@2") (pinfunction "P$2_P$2@2") (pintype "bidirectional"))
      (node (ref "U$30") (pin "P$4@2") (pinfunction "P$4_P$4@2") (pintype "bidirectional"))
      (node (ref "U$31") (pin "P$1@2") (pinfunction "P$1_P$1@2") (pintype "bidirectional"))
      (node (ref "U$32") (pin "P$2@2") (pinfunction "P$2_P$2@2") (pintype "bidirectional"))
      (node (ref "U$32") (pin "P$4@2") (pinfunction "P$4_P$4@2") (pintype "bidirectional"))
      (node (ref "U$33") (pin "P$1@2") (pinfunction "P$1_P$1@2") (pintype "bidirectional"))
      (node (ref "U$35") (pin "P$4") (pinfunction "P$4_P$4") (pintype "bidirectional"))
      (node (ref "U$36") (pin "P$4") (pinfunction "P$4_P$4") (pintype "bidirectional"))
      (node (ref "U$37") (pin "P$4") (pinfunction "P$4_P$4") (pintype "bidirectional"))
      (node (ref "U$4") (pin "P$10") (pinfunction "GND_P$10") (pintype "bidirectional"))
      (node (ref "U$4") (pin "P$11") (pinfunction "GND_P$11") (pintype "bidirectional"))
      (node (ref "U$4") (pin "P$13") (pinfunction "GND_P$13") (pintype "bidirectional"))
      (node (ref "U$4") (pin "P$25") (pinfunction "GND_P$25") (pintype "bidirectional"))
      (node (ref "U$4") (pin "P$49") (pinfunction "GND_P$49") (pintype "bidirectional"))
      (node (ref "U$4") (pin "P$53") (pinfunction "GND_P$53") (pintype "bidirectional"))
      (node (ref "U$4") (pin "P$60") (pinfunction "GND_P$60") (pintype "bidirectional"))
      (node (ref "U$4") (pin "P$9") (pinfunction "GND_P$9") (pintype "bidirectional"))
      (node (ref "U$42") (pin "P$2") (pinfunction "P$2_P$2") (pintype "bidirectional"))
      (node (ref "U$5") (pin "P$10") (pinfunction "GND_P$10") (pintype "bidirectional"))
      (node (ref "U$5") (pin "P$11") (pinfunction "GND_P$11") (pintype "bidirectional"))
      (node (ref "U$5") (pin "P$13") (pinfunction "GND_P$13") (pintype "bidirectional"))
      (node (ref "U$5") (pin "P$25") (pinfunction "GND_P$25") (pintype "bidirectional"))
      (node (ref "U$5") (pin "P$49") (pinfunction "GND_P$49") (pintype "bidirectional"))
      (node (ref "U$5") (pin "P$53") (pinfunction "GND_P$53") (pintype "bidirectional"))
      (node (ref "U$5") (pin "P$60") (pinfunction "GND_P$60") (pintype "bidirectional"))
      (node (ref "U$5") (pin "P$9") (pinfunction "GND_P$9") (pintype "bidirectional"))
      (node (ref "U$6") (pin "P$10") (pinfunction "GND_P$10") (pintype "bidirectional"))
      (node (ref "U$6") (pin "P$11") (pinfunction "GND_P$11") (pintype "bidirectional"))
      (node (ref "U$6") (pin "P$13") (pinfunction "GND_P$13") (pintype "bidirectional"))
      (node (ref "U$6") (pin "P$25") (pinfunction "GND_P$25") (pintype "bidirectional"))
      (node (ref "U$6") (pin "P$49") (pinfunction "GND_P$49") (pintype "bidirectional"))
      (node (ref "U$6") (pin "P$53") (pinfunction "GND_P$53") (pintype "bidirectional"))
      (node (ref "U$6") (pin "P$60") (pinfunction "GND_P$60") (pintype "bidirectional"))
      (node (ref "U$6") (pin "P$9") (pinfunction "GND_P$9") (pintype "bidirectional"))
      (node (ref "U$7") (pin "P$10") (pinfunction "GND_P$10") (pintype "bidirectional"))
      (node (ref "U$7") (pin "P$11") (pinfunction "GND_P$11") (pintype "bidirectional"))
      (node (ref "U$7") (pin "P$13") (pinfunction "GND_P$13") (pintype "bidirectional"))
      (node (ref "U$7") (pin "P$25") (pinfunction "GND_P$25") (pintype "bidirectional"))
      (node (ref "U$7") (pin "P$49") (pinfunction "GND_P$49") (pintype "bidirectional"))
      (node (ref "U$7") (pin "P$53") (pinfunction "GND_P$53") (pintype "bidirectional"))
      (node (ref "U$7") (pin "P$60") (pinfunction "GND_P$60") (pintype "bidirectional"))
      (node (ref "U$7") (pin "P$9") (pinfunction "GND_P$9") (pintype "bidirectional"))
      (node (ref "U$8") (pin "P$10") (pinfunction "GND_P$10") (pintype "bidirectional"))
      (node (ref "U$8") (pin "P$11") (pinfunction "GND_P$11") (pintype "bidirectional"))
      (node (ref "U$8") (pin "P$13") (pinfunction "GND_P$13") (pintype "bidirectional"))
      (node (ref "U$8") (pin "P$25") (pinfunction "GND_P$25") (pintype "bidirectional"))
      (node (ref "U$8") (pin "P$49") (pinfunction "GND_P$49") (pintype "bidirectional"))
      (node (ref "U$8") (pin "P$53") (pinfunction "GND_P$53") (pintype "bidirectional"))
      (node (ref "U$8") (pin "P$60") (pinfunction "GND_P$60") (pintype "bidirectional"))
      (node (ref "U$8") (pin "P$9") (pinfunction "GND_P$9") (pintype "bidirectional"))
    )
    (net (code "69") (name "LIM_X") (class "Default")
      (node (ref "M1") (pin "D9") (pinfunction "D9_D9") (pintype "bidirectional"))
      (node (ref "R3") (pin "2") (pinfunction "2_2") (pintype "passive"))
      (node (ref "U$18") (pin "P$3") (pinfunction "OUT_P$3") (pintype "bidirectional"))
      (node (ref "U$8") (pin "P$29") (pinfunction "OPEN_1_P$29") (pintype "bidirectional"))
    )
    (net (code "70") (name "LIM_Y") (class "Default")
      (node (ref "M1") (pin "D10") (pinfunction "D10_D10") (pintype "bidirectional"))
      (node (ref "R2") (pin "2") (pinfunction "2_2") (pintype "passive"))
      (node (ref "U$13") (pin "P$3@2") (pinfunction "P$3_P$3@2") (pintype "bidirectional"))
      (node (ref "U$16") (pin "P$3@2") (pinfunction "P$3_P$3@2") (pintype "bidirectional"))
      (node (ref "U$19") (pin "P$3") (pinfunction "OUT_P$3") (pintype "bidirectional"))
      (node (ref "U$8") (pin "P$61") (pinfunction "OPEN_2_P$61") (pintype "bidirectional"))
    )
    (net (code "71") (name "LIM_Z") (class "Default")
      (node (ref "M1") (pin "D11") (pinfunction "D11_D11") (pintype "bidirectional"))
      (node (ref "R1") (pin "2") (pinfunction "2_2") (pintype "passive"))
      (node (ref "U$10") (pin "P$1") (pinfunction "P$1_P$1") (pintype "bidirectional"))
      (node (ref "U$14") (pin "P$1") (pinfunction "P$1_P$1") (pintype "bidirectional"))
      (node (ref "U$20") (pin "P$3") (pinfunction "OUT_P$3") (pintype "bidirectional"))
      (node (ref "U$8") (pin "P$30") (pinfunction "OPEN_3_P$30") (pintype "bidirectional"))
    )
    (net (code "72") (name "M8") (class "Default")
      (node (ref "R14") (pin "1") (pinfunction "1_1") (pintype "passive"))
      (node (ref "U$8") (pin "P$32") (pinfunction "OPEN_7_P$32") (pintype "bidirectional"))
    )
    (net (code "73") (name "N$9") (class "Default")
      (node (ref "R15") (pin "1") (pinfunction "1_1") (pintype "passive"))
    )
    (net (code "74") (name "Net-(L1-PadC)") (class "Default")
      (node (ref "L1") (pin "C") (pinfunction "C_C") (pintype "passive"))
      (node (ref "R6") (pin "2") (pinfunction "2_2") (pintype "passive"))
    )
    (net (code "75") (name "Net-(L2-PadC)") (class "Default")
      (node (ref "L2") (pin "C") (pinfunction "C_C") (pintype "passive"))
      (node (ref "R7") (pin "2") (pinfunction "2_2") (pintype "passive"))
    )
    (net (code "76") (name "Net-(L3-PadC)") (class "Default")
      (node (ref "L3") (pin "C") (pinfunction "C_C") (pintype "passive"))
      (node (ref "R8") (pin "2") (pinfunction "2_2") (pintype "passive"))
    )
    (net (code "77") (name "Net-(M1-A4{slash}SDA)") (class "Default")
      (node (ref "M1") (pin "A4") (pinfunction "A4/SDA_A4") (pintype "bidirectional"))
      (node (ref "R15") (pin "2") (pinfunction "2_2") (pintype "passive"))
    )
    (net (code "78") (name "Net-(M1-A5{slash}SCL)") (class "Default")
      (node (ref "M1") (pin "A5") (pinfunction "A5/SCL_A5") (pintype "bidirectional"))
      (node (ref "R16") (pin "2") (pinfunction "2_2") (pintype "passive"))
    )
    (net (code "79") (name "Net-(M1-PadA0)") (class "Default")
      (node (ref "M1") (pin "A0") (pinfunction "A0_A0") (pintype "bidirectional"))
      (node (ref "R11") (pin "2") (pinfunction "2_2") (pintype "passive"))
    )
    (net (code "80") (name "Net-(M1-PadA1)") (class "Default")
      (node (ref "M1") (pin "A1") (pinfunction "A1_A1") (pintype "bidirectional"))
      (node (ref "R12") (pin "2") (pinfunction "2_2") (pintype "passive"))
    )
    (net (code "81") (name "Net-(M1-PadA2)") (class "Default")
      (node (ref "M1") (pin "A2") (pinfunction "A2_A2") (pintype "bidirectional"))
      (node (ref "R13") (pin "2") (pinfunction "2_2") (pintype "passive"))
    )
    (net (code "82") (name "Net-(M1-PadA3)") (class "Default")
      (node (ref "M1") (pin "A3") (pinfunction "A3_A3") (pintype "bidirectional"))
      (node (ref "R14") (pin "2") (pinfunction "2_2") (pintype "passive"))
    )
    (net (code "83") (name "PAUSE") (class "Default")
      (node (ref "Q1") (pin "3") (pinfunction "D_3") (pintype "bidirectional"))
      (node (ref "R12") (pin "1") (pinfunction "1_1") (pintype "passive"))
      (node (ref "U$30") (pin "P$6@2") (pinfunction "P$6_P$6@2") (pintype "bidirectional"))
      (node (ref "U$31") (pin "P$3@2") (pinfunction "P$3_P$3@2") (pintype "bidirectional"))
      (node (ref "U$32") (pin "P$6@2") (pinfunction "P$6_P$6@2") (pintype "bidirectional"))
      (node (ref "U$33") (pin "P$3@2") (pinfunction "P$3_P$3@2") (pintype "bidirectional"))
      (node (ref "U$36") (pin "P$2") (pinfunction "P$2_P$2") (pintype "bidirectional"))
      (node (ref "U$8") (pin "P$31") (pinfunction "OPEN_5_P$31") (pintype "bidirectional"))
    )
    (net (code "84") (name "PAUSE_INVERT") (class "Default")
      (node (ref "Q1") (pin "1") (pinfunction "G_1") (pintype "bidirectional"))
      (node (ref "R4") (pin "2") (pinfunction "2_2") (pintype "passive"))
      (node (ref "U$21") (pin "P$3") (pinfunction "OUT_P$3") (pintype "bidirectional"))
      (node (ref "U$30") (pin "P$3@2") (pinfunction "P$3_P$3@2") (pintype "bidirectional"))
      (node (ref "U$32") (pin "P$3@2") (pinfunction "P$3_P$3@2") (pintype "bidirectional"))
    )
    (net (code "85") (name "POWER") (class "Default")
      (node (ref "CN1") (pin "PWR1") (pinfunction "PWR_PWR1") (pintype "power_in"))
      (node (ref "U$41") (pin "P$3") (pinfunction "P$1_P$3") (pintype "bidirectional"))
    )
    (net (code "86") (name "PROBE") (class "Default")
      (node (ref "R16") (pin "1") (pinfunction "1_1") (pintype "passive"))
      (node (ref "R5") (pin "2") (pinfunction "2_2") (pintype "passive"))
      (node (ref "U$40") (pin "P$1@2") (pinfunction "P$1_P$1@2") (pintype "bidirectional"))
      (node (ref "U$8") (pin "P$64") (pinfunction "OPEN_8_P$64") (pintype "bidirectional"))
    )
    (net (code "87") (name "SP_A1") (class "Default")
      (node (ref "U$11") (pin "P$1") (pinfunction "P$1_P$1") (pintype "bidirectional"))
      (node (ref "U$11") (pin "P$2") (pinfunction "P$2_P$2") (pintype "bidirectional"))
      (node (ref "U$12") (pin "P$2") (pinfunction "PIN_1_P$2") (pintype "bidirectional"))
      (node (ref "U$15") (pin "P$1") (pinfunction "P$1_P$1") (pintype "bidirectional"))
      (node (ref "U$15") (pin "P$2") (pinfunction "P$2_P$2") (pintype "bidirectional"))
      (node (ref "U$5") (pin "P$33") (pinfunction "A1_P$33") (pintype "bidirectional"))
      (node (ref "U$5") (pin "P$34") (pinfunction "A2_P$34") (pintype "bidirectional"))
    )
    (net (code "88") (name "SP_A2") (class "Default")
      (node (ref "U$11") (pin "P$3") (pinfunction "P$3_P$3") (pintype "bidirectional"))
      (node (ref "U$11") (pin "P$4") (pinfunction "P$4_P$4") (pintype "bidirectional"))
      (node (ref "U$12") (pin "P$11") (pinfunction "PIN_2_P$11") (pintype "bidirectional"))
      (node (ref "U$15") (pin "P$3") (pinfunction "P$3_P$3") (pintype "bidirectional"))
      (node (ref "U$15") (pin "P$4") (pinfunction "P$4_P$4") (pintype "bidirectional"))
      (node (ref "U$5") (pin "P$35") (pinfunction "A3_P$35") (pintype "bidirectional"))
      (node (ref "U$5") (pin "P$36") (pinfunction "A4_P$36") (pintype "bidirectional"))
    )
    (net (code "89") (name "SP_A3") (class "Default")
      (node (ref "U$11") (pin "P$5") (pinfunction "P$5_P$5") (pintype "bidirectional"))
      (node (ref "U$11") (pin "P$6") (pinfunction "P$6_P$6") (pintype "bidirectional"))
      (node (ref "U$15") (pin "P$5") (pinfunction "P$5_P$5") (pintype "bidirectional"))
      (node (ref "U$15") (pin "P$6") (pinfunction "P$6_P$6") (pintype "bidirectional"))
      (node (ref "U$17") (pin "P$2") (pinfunction "PIN_1_P$2") (pintype "bidirectional"))
      (node (ref "U$5") (pin "P$37") (pinfunction "A5_P$37") (pintype "bidirectional"))
      (node (ref "U$5") (pin "P$38") (pinfunction "A6_P$38") (pintype "bidirectional"))
    )
    (net (code "90") (name "SP_A4") (class "Default")
      (node (ref "U$11") (pin "P$7") (pinfunction "P$7_P$7") (pintype "bidirectional"))
      (node (ref "U$11") (pin "P$8") (pinfunction "P$8_P$8") (pintype "bidirectional"))
      (node (ref "U$15") (pin "P$7") (pinfunction "P$7_P$7") (pintype "bidirectional"))
      (node (ref "U$15") (pin "P$8") (pinfunction "P$8_P$8") (pintype "bidirectional"))
      (node (ref "U$17") (pin "P$11") (pinfunction "PIN_2_P$11") (pintype "bidirectional"))
      (node (ref "U$5") (pin "P$39") (pinfunction "A7_P$39") (pintype "bidirectional"))
      (node (ref "U$5") (pin "P$40") (pinfunction "A8_P$40") (pintype "bidirectional"))
    )
    (net (code "91") (name "SP_B1") (class "Default")
      (node (ref "U$5") (pin "P$1") (pinfunction "B1_P$1") (pintype "bidirectional"))
    )
    (net (code "92") (name "SP_B2") (class "Default")
      (node (ref "U$5") (pin "P$2") (pinfunction "B2_P$2") (pintype "bidirectional"))
    )
    (net (code "93") (name "SP_B3") (class "Default")
      (node (ref "U$5") (pin "P$3") (pinfunction "B3_P$3") (pintype "bidirectional"))
    )
    (net (code "94") (name "SP_B4") (class "Default")
      (node (ref "U$5") (pin "P$4") (pinfunction "B4_P$4") (pintype "bidirectional"))
    )
    (net (code "95") (name "SP_B5") (class "Default")
      (node (ref "U$5") (pin "P$5") (pinfunction "B5_P$5") (pintype "bidirectional"))
    )
    (net (code "96") (name "SP_B6") (class "Default")
      (node (ref "U$5") (pin "P$6") (pinfunction "B6_P$6") (pintype "bidirectional"))
    )
    (net (code "97") (name "SP_B7") (class "Default")
      (node (ref "U$5") (pin "P$7") (pinfunction "B7_P$7") (pintype "bidirectional"))
    )
    (net (code "98") (name "SP_B8") (class "Default")
      (node (ref "U$5") (pin "P$8") (pinfunction "B8_P$8") (pintype "bidirectional"))
    )
    (net (code "99") (name "SP_DIR") (class "Default")
      (node (ref "M1") (pin "D13") (pinfunction "D13_D13") (pintype "bidirectional"))
      (node (ref "U$8") (pin "P$27") (pinfunction "DIR_4_P$27") (pintype "bidirectional"))
    )
    (net (code "100") (name "SP_PWM") (class "Default")
      (node (ref "M1") (pin "D12") (pinfunction "D12_D12") (pintype "bidirectional"))
      (node (ref "U$8") (pin "P$55") (pinfunction "STEP_4_P$55") (pintype "bidirectional"))
    )
    (net (code "101") (name "START") (class "Default")
      (node (ref "R13") (pin "1") (pinfunction "1_1") (pintype "passive"))
      (node (ref "U$30") (pin "P$7@2") (pinfunction "P$7_P$7@2") (pintype "bidirectional"))
      (node (ref "U$31") (pin "P$4@2") (pinfunction "P$4_P$4@2") (pintype "bidirectional"))
      (node (ref "U$32") (pin "P$7@2") (pinfunction "P$7_P$7@2") (pintype "bidirectional"))
      (node (ref "U$33") (pin "P$4@2") (pinfunction "P$4_P$4@2") (pintype "bidirectional"))
      (node (ref "U$35") (pin "P$2") (pinfunction "P$2_P$2") (pintype "bidirectional"))
      (node (ref "U$8") (pin "P$63") (pinfunction "OPEN_6_P$63") (pintype "bidirectional"))
    )
    (net (code "102") (name "STEP_Y") (class "Default")
      (node (ref "M1") (pin "D3") (pinfunction "D3_D3") (pintype "bidirectional"))
      (node (ref "U$8") (pin "P$54") (pinfunction "STEP_2_P$54") (pintype "bidirectional"))
    )
    (net (code "103") (name "STEP_Z") (class "Default")
      (node (ref "M1") (pin "D4") (pinfunction "D4_D4") (pintype "bidirectional"))
      (node (ref "U$8") (pin "P$23") (pinfunction "STEP_3_P$23") (pintype "bidirectional"))
    )
    (net (code "104") (name "STOP") (class "Default")
      (node (ref "R11") (pin "1") (pinfunction "1_1") (pintype "passive"))
      (node (ref "U$30") (pin "P$5@2") (pinfunction "P$5_P$5@2") (pintype "bidirectional"))
      (node (ref "U$31") (pin "P$2@2") (pinfunction "P$2_P$2@2") (pintype "bidirectional"))
      (node (ref "U$32") (pin "P$5@2") (pinfunction "P$5_P$5@2") (pintype "bidirectional"))
      (node (ref "U$33") (pin "P$2@2") (pinfunction "P$2_P$2@2") (pintype "bidirectional"))
      (node (ref "U$37") (pin "P$2") (pinfunction "P$2_P$2") (pintype "bidirectional"))
      (node (ref "U$8") (pin "P$62") (pinfunction "OPEN_4_P$62") (pintype "bidirectional"))
    )
    (net (code "105") (name "VCC") (class "Default")
      (node (ref "U$2") (pin "P$41") (pinfunction "VCC_P$41") (pintype "bidirectional"))
      (node (ref "U$2") (pin "P$42") (pinfunction "VCC_P$42") (pintype "bidirectional"))
      (node (ref "U$2") (pin "P$43") (pinfunction "VCC_P$43") (pintype "bidirectional"))
      (node (ref "U$3") (pin "P$41") (pinfunction "VCC_P$41") (pintype "bidirectional"))
      (node (ref "U$3") (pin "P$42") (pinfunction "VCC_P$42") (pintype "bidirectional"))
      (node (ref "U$3") (pin "P$43") (pinfunction "VCC_P$43") (pintype "bidirectional"))
      (node (ref "U$4") (pin "P$41") (pinfunction "VCC_P$41") (pintype "bidirectional"))
      (node (ref "U$4") (pin "P$42") (pinfunction "VCC_P$42") (pintype "bidirectional"))
      (node (ref "U$4") (pin "P$43") (pinfunction "VCC_P$43") (pintype "bidirectional"))
      (node (ref "U$41") (pin "P$4") (pinfunction "P$3_P$4") (pintype "bidirectional"))
      (node (ref "U$5") (pin "P$41") (pinfunction "VCC_P$41") (pintype "bidirectional"))
      (node (ref "U$5") (pin "P$42") (pinfunction "VCC_P$42") (pintype "bidirectional"))
      (node (ref "U$5") (pin "P$43") (pinfunction "VCC_P$43") (pintype "bidirectional"))
      (node (ref "U$6") (pin "P$41") (pinfunction "VCC_P$41") (pintype "bidirectional"))
      (node (ref "U$6") (pin "P$42") (pinfunction "VCC_P$42") (pintype "bidirectional"))
      (node (ref "U$6") (pin "P$43") (pinfunction "VCC_P$43") (pintype "bidirectional"))
      (node (ref "U$7") (pin "P$41") (pinfunction "VCC_P$41") (pintype "bidirectional"))
      (node (ref "U$7") (pin "P$42") (pinfunction "VCC_P$42") (pintype "bidirectional"))
      (node (ref "U$7") (pin "P$43") (pinfunction "VCC_P$43") (pintype "bidirectional"))
      (node (ref "U$8") (pin "P$41") (pinfunction "VCC_P$41") (pintype "bidirectional"))
      (node (ref "U$8") (pin "P$42") (pinfunction "VCC_P$42") (pintype "bidirectional"))
      (node (ref "U$8") (pin "P$43") (pinfunction "VCC_P$43") (pintype "bidirectional"))
    )
    (net (code "107") (name "X_B1") (class "Default")
      (node (ref "JP3") (pin "1") (pinfunction "1_1") (pintype "passive"))
      (node (ref "U$8") (pin "P$1") (pinfunction "B1_P$1") (pintype "bidirectional"))
    )
    (net (code "108") (name "X_B2") (class "Default")
      (node (ref "JP3") (pin "2") (pinfunction "2_2") (pintype "passive"))
      (node (ref "U$8") (pin "P$2") (pinfunction "B2_P$2") (pintype "bidirectional"))
    )
    (net (code "109") (name "X_B3") (class "Default")
      (node (ref "JP3") (pin "3") (pinfunction "3_3") (pintype "passive"))
      (node (ref "U$8") (pin "P$3") (pinfunction "B3_P$3") (pintype "bidirectional"))
    )
    (net (code "110") (name "X_B4") (class "Default")
      (node (ref "JP3") (pin "4") (pinfunction "4_4") (pintype "passive"))
      (node (ref "U$8") (pin "P$4") (pinfunction "B4_P$4") (pintype "bidirectional"))
    )
    (net (code "111") (name "X_B5") (class "Default")
      (node (ref "JP3") (pin "5") (pinfunction "5_5") (pintype "passive"))
      (node (ref "U$8") (pin "P$5") (pinfunction "B5_P$5") (pintype "bidirectional"))
    )
    (net (code "112") (name "X_B6") (class "Default")
      (node (ref "JP3") (pin "6") (pinfunction "6_6") (pintype "passive"))
      (node (ref "U$8") (pin "P$6") (pinfunction "B6_P$6") (pintype "bidirectional"))
    )
    (net (code "113") (name "X_B7") (class "Default")
      (node (ref "JP3") (pin "7") (pinfunction "7_7") (pintype "passive"))
      (node (ref "U$8") (pin "P$7") (pinfunction "B7_P$7") (pintype "bidirectional"))
    )
    (net (code "114") (name "X_B8") (class "Default")
      (node (ref "JP3") (pin "8") (pinfunction "8_8") (pintype "passive"))
      (node (ref "U$8") (pin "P$8") (pinfunction "B8_P$8") (pintype "bidirectional"))
    )
    (net (code "115") (name "Y_A1") (class "Default")
      (node (ref "U$7") (pin "P$33") (pinfunction "A1_P$33") (pintype "bidirectional"))
      (node (ref "U$7") (pin "P$34") (pinfunction "A2_P$34") (pintype "bidirectional"))
      (node (ref "U$9") (pin "P$1@2") (pinfunction "P$1_P$1@2") (pintype "bidirectional"))
    )
    (net (code "116") (name "Y_A2") (class "Default")
      (node (ref "U$7") (pin "P$35") (pinfunction "A3_P$35") (pintype "bidirectional"))
      (node (ref "U$7") (pin "P$36") (pinfunction "A4_P$36") (pintype "bidirectional"))
      (node (ref "U$9") (pin "P$2@2") (pinfunction "P$2_P$2@2") (pintype "bidirectional"))
    )
    (net (code "117") (name "Y_A3") (class "Default")
      (node (ref "U$7") (pin "P$37") (pinfunction "A5_P$37") (pintype "bidirectional"))
      (node (ref "U$7") (pin "P$38") (pinfunction "A6_P$38") (pintype "bidirectional"))
      (node (ref "U$9") (pin "P$3@2") (pinfunction "P$3_P$3@2") (pintype "bidirectional"))
    )
    (net (code "118") (name "Y_A4") (class "Default")
      (node (ref "U$7") (pin "P$39") (pinfunction "A7_P$39") (pintype "bidirectional"))
      (node (ref "U$7") (pin "P$40") (pinfunction "A8_P$40") (pintype "bidirectional"))
      (node (ref "U$9") (pin "P$4@2") (pinfunction "P$4_P$4@2") (pintype "bidirectional"))
    )
    (net (code "119") (name "Y_B1") (class "Default")
      (node (ref "JP4") (pin "1") (pinfunction "1_1") (pintype "passive"))
      (node (ref "U$7") (pin "P$1") (pinfunction "B1_P$1") (pintype "bidirectional"))
    )
    (net (code "120") (name "Y_B2") (class "Default")
      (node (ref "JP4") (pin "2") (pinfunction "2_2") (pintype "passive"))
      (node (ref "U$7") (pin "P$2") (pinfunction "B2_P$2") (pintype "bidirectional"))
    )
    (net (code "121") (name "Y_B3") (class "Default")
      (node (ref "JP4") (pin "3") (pinfunction "3_3") (pintype "passive"))
      (node (ref "U$7") (pin "P$3") (pinfunction "B3_P$3") (pintype "bidirectional"))
    )
    (net (code "122") (name "Y_B4") (class "Default")
      (node (ref "JP4") (pin "4") (pinfunction "4_4") (pintype "passive"))
      (node (ref "U$7") (pin "P$4") (pinfunction "B4_P$4") (pintype "bidirectional"))
    )
    (net (code "123") (name "Y_B5") (class "Default")
      (node (ref "JP4") (pin "5") (pinfunction "5_5") (pintype "passive"))
      (node (ref "U$7") (pin "P$5") (pinfunction "B5_P$5") (pintype "bidirectional"))
    )
    (net (code "124") (name "Y_B6") (class "Default")
      (node (ref "JP4") (pin "6") (pinfunction "6_6") (pintype "passive"))
      (node (ref "U$7") (pin "P$6") (pinfunction "B6_P$6") (pintype "bidirectional"))
    )
    (net (code "125") (name "Y_B7") (class "Default")
      (node (ref "JP4") (pin "7") (pinfunction "7_7") (pintype "passive"))
      (node (ref "U$7") (pin "P$7") (pinfunction "B7_P$7") (pintype "bidirectional"))
    )
    (net (code "126") (name "Y_B8") (class "Default")
      (node (ref "JP4") (pin "8") (pinfunction "8_8") (pintype "passive"))
      (node (ref "U$7") (pin "P$8") (pinfunction "B8_P$8") (pintype "bidirectional"))
    )
    (net (code "127") (name "Z_A1") (class "Default")
      (node (ref "U$10") (pin "P$5") (pinfunction "P$5_P$5") (pintype "bidirectional"))
      (node (ref "U$14") (pin "P$5") (pinfunction "P$5_P$5") (pintype "bidirectional"))
      (node (ref "U$34") (pin "P$1@2") (pinfunction "P$1_P$1@2") (pintype "bidirectional"))
      (node (ref "U$6") (pin "P$33") (pinfunction "A1_P$33") (pintype "bidirectional"))
      (node (ref "U$6") (pin "P$34") (pinfunction "A2_P$34") (pintype "bidirectional"))
    )
    (net (code "128") (name "Z_A2") (class "Default")
      (node (ref "U$10") (pin "P$6") (pinfunction "P$6_P$6") (pintype "bidirectional"))
      (node (ref "U$14") (pin "P$6") (pinfunction "P$6_P$6") (pintype "bidirectional"))
      (node (ref "U$34") (pin "P$2@2") (pinfunction "P$2_P$2@2") (pintype "bidirectional"))
      (node (ref "U$6") (pin "P$35") (pinfunction "A3_P$35") (pintype "bidirectional"))
      (node (ref "U$6") (pin "P$36") (pinfunction "A4_P$36") (pintype "bidirectional"))
    )
    (net (code "129") (name "Z_A3") (class "Default")
      (node (ref "U$10") (pin "P$7") (pinfunction "P$7_P$7") (pintype "bidirectional"))
      (node (ref "U$14") (pin "P$7") (pinfunction "P$7_P$7") (pintype "bidirectional"))
      (node (ref "U$34") (pin "P$3@2") (pinfunction "P$3_P$3@2") (pintype "bidirectional"))
      (node (ref "U$6") (pin "P$37") (pinfunction "A5_P$37") (pintype "bidirectional"))
      (node (ref "U$6") (pin "P$38") (pinfunction "A6_P$38") (pintype "bidirectional"))
    )
    (net (code "130") (name "Z_A4") (class "Default")
      (node (ref "U$10") (pin "P$8") (pinfunction "P$8_P$8") (pintype "bidirectional"))
      (node (ref "U$14") (pin "P$8") (pinfunction "P$8_P$8") (pintype "bidirectional"))
      (node (ref "U$34") (pin "P$4@2") (pinfunction "P$4_P$4@2") (pintype "bidirectional"))
      (node (ref "U$6") (pin "P$39") (pinfunction "A7_P$39") (pintype "bidirectional"))
      (node (ref "U$6") (pin "P$40") (pinfunction "A8_P$40") (pintype "bidirectional"))
    )
    (net (code "131") (name "Z_B1") (class "Default")
      (node (ref "JP5") (pin "1") (pinfunction "1_1") (pintype "passive"))
      (node (ref "U$6") (pin "P$1") (pinfunction "B1_P$1") (pintype "bidirectional"))
    )
    (net (code "132") (name "Z_B2") (class "Default")
      (node (ref "JP5") (pin "2") (pinfunction "2_2") (pintype "passive"))
      (node (ref "U$6") (pin "P$2") (pinfunction "B2_P$2") (pintype "bidirectional"))
    )
    (net (code "133") (name "Z_B3") (class "Default")
      (node (ref "JP5") (pin "3") (pinfunction "3_3") (pintype "passive"))
      (node (ref "U$6") (pin "P$3") (pinfunction "B3_P$3") (pintype "bidirectional"))
    )
    (net (code "134") (name "Z_B4") (class "Default")
      (node (ref "JP5") (pin "4") (pinfunction "4_4") (pintype "passive"))
      (node (ref "U$6") (pin "P$4") (pinfunction "B4_P$4") (pintype "bidirectional"))
    )
    (net (code "135") (name "Z_B5") (class "Default")
      (node (ref "JP5") (pin "5") (pinfunction "5_5") (pintype "passive"))
      (node (ref "U$6") (pin "P$5") (pinfunction "B5_P$5") (pintype "bidirectional"))
    )
    (net (code "136") (name "Z_B6") (class "Default")
      (node (ref "JP5") (pin "6") (pinfunction "6_6") (pintype "passive"))
      (node (ref "U$6") (pin "P$6") (pinfunction "B6_P$6") (pintype "bidirectional"))
    )
    (net (code "137") (name "Z_B7") (class "Default")
      (node (ref "JP5") (pin "7") (pinfunction "7_7") (pintype "passive"))
      (node (ref "U$6") (pin "P$7") (pinfunction "B7_P$7") (pintype "bidirectional"))
    )
    (net (code "138") (name "Z_B8") (class "Default")
      (node (ref "JP5") (pin "8") (pinfunction "8_8") (pintype "passive"))
      (node (ref "U$6") (pin "P$8") (pinfunction "B8_P$8") (pintype "bidirectional"))
    )
    (net (code "139") (name "unconnected-(M1-5V-Pad5V_ICSP)") (class "Default")
      (node (ref "M1") (pin "5V_ICSP") (pinfunction "5V_5V_ICSP") (pintype "passive"))
    )
    (net (code "140") (name "unconnected-(M1-GND-PadGND@2)") (class "Default")
      (node (ref "M1") (pin "GND@2") (pinfunction "GND_GND@2") (pintype "passive"))
    )
    (net (code "141") (name "unconnected-(M1-PadAREF)") (class "Default")
      (node (ref "M1") (pin "AREF") (pinfunction "AREF_AREF") (pintype "bidirectional"))
    )
    (net (code "142") (name "unconnected-(M1-PadD0)") (class "Default")
      (node (ref "M1") (pin "D0") (pinfunction "D0_D0") (pintype "bidirectional"))
    )
    (net (code "143") (name "unconnected-(M1-PadD1)") (class "Default")
      (node (ref "M1") (pin "D1") (pinfunction "D1_D1") (pintype "bidirectional"))
    )
    (net (code "144") (name "unconnected-(M1-PadIOREF)") (class "Default")
      (node (ref "M1") (pin "IOREF") (pinfunction "IOREF_IOREF") (pintype "output"))
    )
    (net (code "145") (name "unconnected-(M1-PadMISO)") (class "Default")
      (node (ref "M1") (pin "MISO") (pinfunction "MISO_MISO") (pintype "passive"))
    )
    (net (code "146") (name "unconnected-(M1-PadMOSI)") (class "Default")
      (node (ref "M1") (pin "MOSI") (pinfunction "MOSI_MOSI") (pintype "passive"))
    )
    (net (code "147") (name "unconnected-(M1-PadRESERVED)") (class "Default")
      (node (ref "M1") (pin "RESERVED") (pinfunction "RESERVED_RESERVED") (pintype "no_connect"))
    )
    (net (code "148") (name "unconnected-(M1-PadSCK)") (class "Default")
      (node (ref "M1") (pin "SCK") (pinfunction "SCK_SCK") (pintype "passive"))
    )
    (net (code "149") (name "unconnected-(M1-PadSCL)") (class "Default")
      (node (ref "M1") (pin "SCL") (pinfunction "SCL_SCL") (pintype "bidirectional"))
    )
    (net (code "150") (name "unconnected-(M1-PadSDA)") (class "Default")
      (node (ref "M1") (pin "SDA") (pinfunction "SDA_SDA") (pintype "bidirectional"))
    )
    (net (code "151") (name "unconnected-(M1-RST-PadRESET_ICSP)") (class "Default")
      (node (ref "M1") (pin "RESET_ICSP") (pinfunction "RST_RESET_ICSP") (pintype "passive"))
    )
    (net (code "152") (name "unconnected-(M1-{slash}RESET-PadRESET)") (class "Default")
      (node (ref "M1") (pin "RESET") (pinfunction "/RESET_RESET") (pintype "bidirectional"))
    )
    (net (code "153") (name "unconnected-(U$2-3V-PadP$12)") (class "Default")
      (node (ref "U$2") (pin "P$12") (pinfunction "3V_P$12") (pintype "bidirectional"))
    )
    (net (code "154") (name "unconnected-(U$2-5V-PadP$44)") (class "Default")
      (node (ref "U$2") (pin "P$44") (pinfunction "5V_P$44") (pintype "bidirectional"))
    )
    (net (code "155") (name "unconnected-(U$2-DIR_1-PadP$57)") (class "Default")
      (node (ref "U$2") (pin "P$57") (pinfunction "DIR_1_P$57") (pintype "bidirectional"))
    )
    (net (code "156") (name "unconnected-(U$2-DIR_2-PadP$26)") (class "Default")
      (node (ref "U$2") (pin "P$26") (pinfunction "DIR_2_P$26") (pintype "bidirectional"))
    )
    (net (code "157") (name "unconnected-(U$2-DIR_3-PadP$58)") (class "Default")
      (node (ref "U$2") (pin "P$58") (pinfunction "DIR_3_P$58") (pintype "bidirectional"))
    )
    (net (code "158") (name "unconnected-(U$2-DIR_4-PadP$27)") (class "Default")
      (node (ref "U$2") (pin "P$27") (pinfunction "DIR_4_P$27") (pintype "bidirectional"))
    )
    (net (code "159") (name "unconnected-(U$2-DIR_5-PadP$59)") (class "Default")
      (node (ref "U$2") (pin "P$59") (pinfunction "DIR_5_P$59") (pintype "bidirectional"))
    )
    (net (code "160") (name "unconnected-(U$2-DIR_6-PadP$28)") (class "Default")
      (node (ref "U$2") (pin "P$28") (pinfunction "DIR_6_P$28") (pintype "bidirectional"))
    )
    (net (code "161") (name "unconnected-(U$2-ENBL_1-PadP$50)") (class "Default")
      (node (ref "U$2") (pin "P$50") (pinfunction "ENBL_1_P$50") (pintype "bidirectional"))
    )
    (net (code "162") (name "unconnected-(U$2-ENBL_2-PadP$19)") (class "Default")
      (node (ref "U$2") (pin "P$19") (pinfunction "ENBL_2_P$19") (pintype "bidirectional"))
    )
    (net (code "163") (name "unconnected-(U$2-ENBL_3-PadP$51)") (class "Default")
      (node (ref "U$2") (pin "P$51") (pinfunction "ENBL_3_P$51") (pintype "bidirectional"))
    )
    (net (code "164") (name "unconnected-(U$2-ENBL_4-PadP$20)") (class "Default")
      (node (ref "U$2") (pin "P$20") (pinfunction "ENBL_4_P$20") (pintype "bidirectional"))
    )
    (net (code "165") (name "unconnected-(U$2-ENBL_5-PadP$52)") (class "Default")
      (node (ref "U$2") (pin "P$52") (pinfunction "ENBL_5_P$52") (pintype "bidirectional"))
    )
    (net (code "166") (name "unconnected-(U$2-ENBL_6-PadP$21)") (class "Default")
      (node (ref "U$2") (pin "P$21") (pinfunction "ENBL_6_P$21") (pintype "bidirectional"))
    )
    (net (code "167") (name "unconnected-(U$2-LATCH_1-PadP$46)") (class "Default")
      (node (ref "U$2") (pin "P$46") (pinfunction "LATCH_1_P$46") (pintype "bidirectional"))
    )
    (net (code "168") (name "unconnected-(U$2-LATCH_2-PadP$15)") (class "Default")
      (node (ref "U$2") (pin "P$15") (pinfunction "LATCH_2_P$15") (pintype "bidirectional"))
    )
    (net (code "169") (name "unconnected-(U$2-LATCH_3-PadP$47)") (class "Default")
      (node (ref "U$2") (pin "P$47") (pinfunction "LATCH_3_P$47") (pintype "bidirectional"))
    )
    (net (code "170") (name "unconnected-(U$2-LATCH_4-PadP$16)") (class "Default")
      (node (ref "U$2") (pin "P$16") (pinfunction "LATCH_4_P$16") (pintype "bidirectional"))
    )
    (net (code "171") (name "unconnected-(U$2-LATCH_5-PadP$48)") (class "Default")
      (node (ref "U$2") (pin "P$48") (pinfunction "LATCH_5_P$48") (pintype "bidirectional"))
    )
    (net (code "172") (name "unconnected-(U$2-LATCH_6-PadP$17)") (class "Default")
      (node (ref "U$2") (pin "P$17") (pinfunction "LATCH_6_P$17") (pintype "bidirectional"))
    )
    (net (code "173") (name "unconnected-(U$2-OPEN_1-PadP$29)") (class "Default")
      (node (ref "U$2") (pin "P$29") (pinfunction "OPEN_1_P$29") (pintype "bidirectional"))
    )
    (net (code "174") (name "unconnected-(U$2-OPEN_2-PadP$61)") (class "Default")
      (node (ref "U$2") (pin "P$61") (pinfunction "OPEN_2_P$61") (pintype "bidirectional"))
    )
    (net (code "175") (name "unconnected-(U$2-OPEN_3-PadP$30)") (class "Default")
      (node (ref "U$2") (pin "P$30") (pinfunction "OPEN_3_P$30") (pintype "bidirectional"))
    )
    (net (code "176") (name "unconnected-(U$2-OPEN_4-PadP$62)") (class "Default")
      (node (ref "U$2") (pin "P$62") (pinfunction "OPEN_4_P$62") (pintype "bidirectional"))
    )
    (net (code "177") (name "unconnected-(U$2-OPEN_5-PadP$31)") (class "Default")
      (node (ref "U$2") (pin "P$31") (pinfunction "OPEN_5_P$31") (pintype "bidirectional"))
    )
    (net (code "178") (name "unconnected-(U$2-OPEN_6-PadP$63)") (class "Default")
      (node (ref "U$2") (pin "P$63") (pinfunction "OPEN_6_P$63") (pintype "bidirectional"))
    )
    (net (code "179") (name "unconnected-(U$2-OPEN_7-PadP$32)") (class "Default")
      (node (ref "U$2") (pin "P$32") (pinfunction "OPEN_7_P$32") (pintype "bidirectional"))
    )
    (net (code "180") (name "unconnected-(U$2-OPEN_8-PadP$64)") (class "Default")
      (node (ref "U$2") (pin "P$64") (pinfunction "OPEN_8_P$64") (pintype "bidirectional"))
    )
    (net (code "181") (name "unconnected-(U$2-RESET-PadP$18)") (class "Default")
      (node (ref "U$2") (pin "P$18") (pinfunction "RESET_P$18") (pintype "bidirectional"))
    )
    (net (code "182") (name "unconnected-(U$2-STEP_1-PadP$22)") (class "Default")
      (node (ref "U$2") (pin "P$22") (pinfunction "STEP_1_P$22") (pintype "bidirectional"))
    )
    (net (code "183") (name "unconnected-(U$2-STEP_2-PadP$54)") (class "Default")
      (node (ref "U$2") (pin "P$54") (pinfunction "STEP_2_P$54") (pintype "bidirectional"))
    )
    (net (code "184") (name "unconnected-(U$2-STEP_3-PadP$23)") (class "Default")
      (node (ref "U$2") (pin "P$23") (pinfunction "STEP_3_P$23") (pintype "bidirectional"))
    )
    (net (code "185") (name "unconnected-(U$2-STEP_4-PadP$55)") (class "Default")
      (node (ref "U$2") (pin "P$55") (pinfunction "STEP_4_P$55") (pintype "bidirectional"))
    )
    (net (code "186") (name "unconnected-(U$2-STEP_5-PadP$24)") (class "Default")
      (node (ref "U$2") (pin "P$24") (pinfunction "STEP_5_P$24") (pintype "bidirectional"))
    )
    (net (code "187") (name "unconnected-(U$2-STEP_6-PadP$56)") (class "Default")
      (node (ref "U$2") (pin "P$56") (pinfunction "STEP_6_P$56") (pintype "bidirectional"))
    )
    (net (code "188") (name "unconnected-(U$2-SYS_CLK-PadP$45)") (class "Default")
      (node (ref "U$2") (pin "P$45") (pinfunction "SYS_CLK_P$45") (pintype "bidirectional"))
    )
    (net (code "189") (name "unconnected-(U$2-SYS_DAT-PadP$14)") (class "Default")
      (node (ref "U$2") (pin "P$14") (pinfunction "SYS_DAT_P$14") (pintype "bidirectional"))
    )
    (net (code "190") (name "unconnected-(U$3-3V-PadP$12)") (class "Default")
      (node (ref "U$3") (pin "P$12") (pinfunction "3V_P$12") (pintype "bidirectional"))
    )
    (net (code "191") (name "unconnected-(U$3-5V-PadP$44)") (class "Default")
      (node (ref "U$3") (pin "P$44") (pinfunction "5V_P$44") (pintype "bidirectional"))
    )
    (net (code "192") (name "unconnected-(U$3-DIR_1-PadP$57)") (class "Default")
      (node (ref "U$3") (pin "P$57") (pinfunction "DIR_1_P$57") (pintype "bidirectional"))
    )
    (net (code "193") (name "unconnected-(U$3-DIR_2-PadP$26)") (class "Default")
      (node (ref "U$3") (pin "P$26") (pinfunction "DIR_2_P$26") (pintype "bidirectional"))
    )
    (net (code "194") (name "unconnected-(U$3-DIR_3-PadP$58)") (class "Default")
      (node (ref "U$3") (pin "P$58") (pinfunction "DIR_3_P$58") (pintype "bidirectional"))
    )
    (net (code "195") (name "unconnected-(U$3-DIR_4-PadP$27)") (class "Default")
      (node (ref "U$3") (pin "P$27") (pinfunction "DIR_4_P$27") (pintype "bidirectional"))
    )
    (net (code "196") (name "unconnected-(U$3-DIR_5-PadP$59)") (class "Default")
      (node (ref "U$3") (pin "P$59") (pinfunction "DIR_5_P$59") (pintype "bidirectional"))
    )
    (net (code "197") (name "unconnected-(U$3-DIR_6-PadP$28)") (class "Default")
      (node (ref "U$3") (pin "P$28") (pinfunction "DIR_6_P$28") (pintype "bidirectional"))
    )
    (net (code "198") (name "unconnected-(U$3-ENBL_1-PadP$50)") (class "Default")
      (node (ref "U$3") (pin "P$50") (pinfunction "ENBL_1_P$50") (pintype "bidirectional"))
    )
    (net (code "199") (name "unconnected-(U$3-ENBL_2-PadP$19)") (class "Default")
      (node (ref "U$3") (pin "P$19") (pinfunction "ENBL_2_P$19") (pintype "bidirectional"))
    )
    (net (code "200") (name "unconnected-(U$3-ENBL_3-PadP$51)") (class "Default")
      (node (ref "U$3") (pin "P$51") (pinfunction "ENBL_3_P$51") (pintype "bidirectional"))
    )
    (net (code "201") (name "unconnected-(U$3-ENBL_4-PadP$20)") (class "Default")
      (node (ref "U$3") (pin "P$20") (pinfunction "ENBL_4_P$20") (pintype "bidirectional"))
    )
    (net (code "202") (name "unconnected-(U$3-ENBL_5-PadP$52)") (class "Default")
      (node (ref "U$3") (pin "P$52") (pinfunction "ENBL_5_P$52") (pintype "bidirectional"))
    )
    (net (code "203") (name "unconnected-(U$3-ENBL_6-PadP$21)") (class "Default")
      (node (ref "U$3") (pin "P$21") (pinfunction "ENBL_6_P$21") (pintype "bidirectional"))
    )
    (net (code "204") (name "unconnected-(U$3-LATCH_1-PadP$46)") (class "Default")
      (node (ref "U$3") (pin "P$46") (pinfunction "LATCH_1_P$46") (pintype "bidirectional"))
    )
    (net (code "205") (name "unconnected-(U$3-LATCH_2-PadP$15)") (class "Default")
      (node (ref "U$3") (pin "P$15") (pinfunction "LATCH_2_P$15") (pintype "bidirectional"))
    )
    (net (code "206") (name "unconnected-(U$3-LATCH_3-PadP$47)") (class "Default")
      (node (ref "U$3") (pin "P$47") (pinfunction "LATCH_3_P$47") (pintype "bidirectional"))
    )
    (net (code "207") (name "unconnected-(U$3-LATCH_4-PadP$16)") (class "Default")
      (node (ref "U$3") (pin "P$16") (pinfunction "LATCH_4_P$16") (pintype "bidirectional"))
    )
    (net (code "208") (name "unconnected-(U$3-LATCH_5-PadP$48)") (class "Default")
      (node (ref "U$3") (pin "P$48") (pinfunction "LATCH_5_P$48") (pintype "bidirectional"))
    )
    (net (code "209") (name "unconnected-(U$3-LATCH_6-PadP$17)") (class "Default")
      (node (ref "U$3") (pin "P$17") (pinfunction "LATCH_6_P$17") (pintype "bidirectional"))
    )
    (net (code "210") (name "unconnected-(U$3-OPEN_1-PadP$29)") (class "Default")
      (node (ref "U$3") (pin "P$29") (pinfunction "OPEN_1_P$29") (pintype "bidirectional"))
    )
    (net (code "211") (name "unconnected-(U$3-OPEN_2-PadP$61)") (class "Default")
      (node (ref "U$3") (pin "P$61") (pinfunction "OPEN_2_P$61") (pintype "bidirectional"))
    )
    (net (code "212") (name "unconnected-(U$3-OPEN_3-PadP$30)") (class "Default")
      (node (ref "U$3") (pin "P$30") (pinfunction "OPEN_3_P$30") (pintype "bidirectional"))
    )
    (net (code "213") (name "unconnected-(U$3-OPEN_4-PadP$62)") (class "Default")
      (node (ref "U$3") (pin "P$62") (pinfunction "OPEN_4_P$62") (pintype "bidirectional"))
    )
    (net (code "214") (name "unconnected-(U$3-OPEN_5-PadP$31)") (class "Default")
      (node (ref "U$3") (pin "P$31") (pinfunction "OPEN_5_P$31") (pintype "bidirectional"))
    )
    (net (code "215") (name "unconnected-(U$3-OPEN_6-PadP$63)") (class "Default")
      (node (ref "U$3") (pin "P$63") (pinfunction "OPEN_6_P$63") (pintype "bidirectional"))
    )
    (net (code "216") (name "unconnected-(U$3-OPEN_7-PadP$32)") (class "Default")
      (node (ref "U$3") (pin "P$32") (pinfunction "OPEN_7_P$32") (pintype "bidirectional"))
    )
    (net (code "217") (name "unconnected-(U$3-OPEN_8-PadP$64)") (class "Default")
      (node (ref "U$3") (pin "P$64") (pinfunction "OPEN_8_P$64") (pintype "bidirectional"))
    )
    (net (code "218") (name "unconnected-(U$3-RESET-PadP$18)") (class "Default")
      (node (ref "U$3") (pin "P$18") (pinfunction "RESET_P$18") (pintype "bidirectional"))
    )
    (net (code "219") (name "unconnected-(U$3-STEP_1-PadP$22)") (class "Default")
      (node (ref "U$3") (pin "P$22") (pinfunction "STEP_1_P$22") (pintype "bidirectional"))
    )
    (net (code "220") (name "unconnected-(U$3-STEP_2-PadP$54)") (class "Default")
      (node (ref "U$3") (pin "P$54") (pinfunction "STEP_2_P$54") (pintype "bidirectional"))
    )
    (net (code "221") (name "unconnected-(U$3-STEP_3-PadP$23)") (class "Default")
      (node (ref "U$3") (pin "P$23") (pinfunction "STEP_3_P$23") (pintype "bidirectional"))
    )
    (net (code "222") (name "unconnected-(U$3-STEP_4-PadP$55)") (class "Default")
      (node (ref "U$3") (pin "P$55") (pinfunction "STEP_4_P$55") (pintype "bidirectional"))
    )
    (net (code "223") (name "unconnected-(U$3-STEP_5-PadP$24)") (class "Default")
      (node (ref "U$3") (pin "P$24") (pinfunction "STEP_5_P$24") (pintype "bidirectional"))
    )
    (net (code "224") (name "unconnected-(U$3-STEP_6-PadP$56)") (class "Default")
      (node (ref "U$3") (pin "P$56") (pinfunction "STEP_6_P$56") (pintype "bidirectional"))
    )
    (net (code "225") (name "unconnected-(U$3-SYS_CLK-PadP$45)") (class "Default")
      (node (ref "U$3") (pin "P$45") (pinfunction "SYS_CLK_P$45") (pintype "bidirectional"))
    )
    (net (code "226") (name "unconnected-(U$3-SYS_DAT-PadP$14)") (class "Default")
      (node (ref "U$3") (pin "P$14") (pinfunction "SYS_DAT_P$14") (pintype "bidirectional"))
    )
    (net (code "227") (name "unconnected-(U$4-3V-PadP$12)") (class "Default")
      (node (ref "U$4") (pin "P$12") (pinfunction "3V_P$12") (pintype "bidirectional"))
    )
    (net (code "228") (name "unconnected-(U$4-5V-PadP$44)") (class "Default")
      (node (ref "U$4") (pin "P$44") (pinfunction "5V_P$44") (pintype "bidirectional"))
    )
    (net (code "229") (name "unconnected-(U$4-DIR_1-PadP$57)") (class "Default")
      (node (ref "U$4") (pin "P$57") (pinfunction "DIR_1_P$57") (pintype "bidirectional"))
    )
    (net (code "230") (name "unconnected-(U$4-DIR_2-PadP$26)") (class "Default")
      (node (ref "U$4") (pin "P$26") (pinfunction "DIR_2_P$26") (pintype "bidirectional"))
    )
    (net (code "231") (name "unconnected-(U$4-DIR_3-PadP$58)") (class "Default")
      (node (ref "U$4") (pin "P$58") (pinfunction "DIR_3_P$58") (pintype "bidirectional"))
    )
    (net (code "232") (name "unconnected-(U$4-DIR_4-PadP$27)") (class "Default")
      (node (ref "U$4") (pin "P$27") (pinfunction "DIR_4_P$27") (pintype "bidirectional"))
    )
    (net (code "233") (name "unconnected-(U$4-DIR_5-PadP$59)") (class "Default")
      (node (ref "U$4") (pin "P$59") (pinfunction "DIR_5_P$59") (pintype "bidirectional"))
    )
    (net (code "234") (name "unconnected-(U$4-DIR_6-PadP$28)") (class "Default")
      (node (ref "U$4") (pin "P$28") (pinfunction "DIR_6_P$28") (pintype "bidirectional"))
    )
    (net (code "235") (name "unconnected-(U$4-ENBL_1-PadP$50)") (class "Default")
      (node (ref "U$4") (pin "P$50") (pinfunction "ENBL_1_P$50") (pintype "bidirectional"))
    )
    (net (code "236") (name "unconnected-(U$4-ENBL_2-PadP$19)") (class "Default")
      (node (ref "U$4") (pin "P$19") (pinfunction "ENBL_2_P$19") (pintype "bidirectional"))
    )
    (net (code "237") (name "unconnected-(U$4-ENBL_3-PadP$51)") (class "Default")
      (node (ref "U$4") (pin "P$51") (pinfunction "ENBL_3_P$51") (pintype "bidirectional"))
    )
    (net (code "238") (name "unconnected-(U$4-ENBL_4-PadP$20)") (class "Default")
      (node (ref "U$4") (pin "P$20") (pinfunction "ENBL_4_P$20") (pintype "bidirectional"))
    )
    (net (code "239") (name "unconnected-(U$4-ENBL_5-PadP$52)") (class "Default")
      (node (ref "U$4") (pin "P$52") (pinfunction "ENBL_5_P$52") (pintype "bidirectional"))
    )
    (net (code "240") (name "unconnected-(U$4-ENBL_6-PadP$21)") (class "Default")
      (node (ref "U$4") (pin "P$21") (pinfunction "ENBL_6_P$21") (pintype "bidirectional"))
    )
    (net (code "241") (name "unconnected-(U$4-LATCH_1-PadP$46)") (class "Default")
      (node (ref "U$4") (pin "P$46") (pinfunction "LATCH_1_P$46") (pintype "bidirectional"))
    )
    (net (code "242") (name "unconnected-(U$4-LATCH_2-PadP$15)") (class "Default")
      (node (ref "U$4") (pin "P$15") (pinfunction "LATCH_2_P$15") (pintype "bidirectional"))
    )
    (net (code "243") (name "unconnected-(U$4-LATCH_3-PadP$47)") (class "Default")
      (node (ref "U$4") (pin "P$47") (pinfunction "LATCH_3_P$47") (pintype "bidirectional"))
    )
    (net (code "244") (name "unconnected-(U$4-LATCH_4-PadP$16)") (class "Default")
      (node (ref "U$4") (pin "P$16") (pinfunction "LATCH_4_P$16") (pintype "bidirectional"))
    )
    (net (code "245") (name "unconnected-(U$4-LATCH_5-PadP$48)") (class "Default")
      (node (ref "U$4") (pin "P$48") (pinfunction "LATCH_5_P$48") (pintype "bidirectional"))
    )
    (net (code "246") (name "unconnected-(U$4-LATCH_6-PadP$17)") (class "Default")
      (node (ref "U$4") (pin "P$17") (pinfunction "LATCH_6_P$17") (pintype "bidirectional"))
    )
    (net (code "247") (name "unconnected-(U$4-OPEN_1-PadP$29)") (class "Default")
      (node (ref "U$4") (pin "P$29") (pinfunction "OPEN_1_P$29") (pintype "bidirectional"))
    )
    (net (code "248") (name "unconnected-(U$4-OPEN_2-PadP$61)") (class "Default")
      (node (ref "U$4") (pin "P$61") (pinfunction "OPEN_2_P$61") (pintype "bidirectional"))
    )
    (net (code "249") (name "unconnected-(U$4-OPEN_3-PadP$30)") (class "Default")
      (node (ref "U$4") (pin "P$30") (pinfunction "OPEN_3_P$30") (pintype "bidirectional"))
    )
    (net (code "250") (name "unconnected-(U$4-OPEN_4-PadP$62)") (class "Default")
      (node (ref "U$4") (pin "P$62") (pinfunction "OPEN_4_P$62") (pintype "bidirectional"))
    )
    (net (code "251") (name "unconnected-(U$4-OPEN_5-PadP$31)") (class "Default")
      (node (ref "U$4") (pin "P$31") (pinfunction "OPEN_5_P$31") (pintype "bidirectional"))
    )
    (net (code "252") (name "unconnected-(U$4-OPEN_6-PadP$63)") (class "Default")
      (node (ref "U$4") (pin "P$63") (pinfunction "OPEN_6_P$63") (pintype "bidirectional"))
    )
    (net (code "253") (name "unconnected-(U$4-OPEN_7-PadP$32)") (class "Default")
      (node (ref "U$4") (pin "P$32") (pinfunction "OPEN_7_P$32") (pintype "bidirectional"))
    )
    (net (code "254") (name "unconnected-(U$4-OPEN_8-PadP$64)") (class "Default")
      (node (ref "U$4") (pin "P$64") (pinfunction "OPEN_8_P$64") (pintype "bidirectional"))
    )
    (net (code "255") (name "unconnected-(U$4-RESET-PadP$18)") (class "Default")
      (node (ref "U$4") (pin "P$18") (pinfunction "RESET_P$18") (pintype "bidirectional"))
    )
    (net (code "256") (name "unconnected-(U$4-STEP_1-PadP$22)") (class "Default")
      (node (ref "U$4") (pin "P$22") (pinfunction "STEP_1_P$22") (pintype "bidirectional"))
    )
    (net (code "257") (name "unconnected-(U$4-STEP_2-PadP$54)") (class "Default")
      (node (ref "U$4") (pin "P$54") (pinfunction "STEP_2_P$54") (pintype "bidirectional"))
    )
    (net (code "258") (name "unconnected-(U$4-STEP_3-PadP$23)") (class "Default")
      (node (ref "U$4") (pin "P$23") (pinfunction "STEP_3_P$23") (pintype "bidirectional"))
    )
    (net (code "259") (name "unconnected-(U$4-STEP_4-PadP$55)") (class "Default")
      (node (ref "U$4") (pin "P$55") (pinfunction "STEP_4_P$55") (pintype "bidirectional"))
    )
    (net (code "260") (name "unconnected-(U$4-STEP_5-PadP$24)") (class "Default")
      (node (ref "U$4") (pin "P$24") (pinfunction "STEP_5_P$24") (pintype "bidirectional"))
    )
    (net (code "261") (name "unconnected-(U$4-STEP_6-PadP$56)") (class "Default")
      (node (ref "U$4") (pin "P$56") (pinfunction "STEP_6_P$56") (pintype "bidirectional"))
    )
    (net (code "262") (name "unconnected-(U$4-SYS_CLK-PadP$45)") (class "Default")
      (node (ref "U$4") (pin "P$45") (pinfunction "SYS_CLK_P$45") (pintype "bidirectional"))
    )
    (net (code "263") (name "unconnected-(U$4-SYS_DAT-PadP$14)") (class "Default")
      (node (ref "U$4") (pin "P$14") (pinfunction "SYS_DAT_P$14") (pintype "bidirectional"))
    )
    (net (code "264") (name "unconnected-(U$5-3V-PadP$12)") (class "Default")
      (node (ref "U$5") (pin "P$12") (pinfunction "3V_P$12") (pintype "bidirectional"))
    )
    (net (code "265") (name "unconnected-(U$5-5V-PadP$44)") (class "Default")
      (node (ref "U$5") (pin "P$44") (pinfunction "5V_P$44") (pintype "bidirectional"))
    )
    (net (code "266") (name "unconnected-(U$5-DIR_1-PadP$57)") (class "Default")
      (node (ref "U$5") (pin "P$57") (pinfunction "DIR_1_P$57") (pintype "bidirectional"))
    )
    (net (code "267") (name "unconnected-(U$5-DIR_2-PadP$26)") (class "Default")
      (node (ref "U$5") (pin "P$26") (pinfunction "DIR_2_P$26") (pintype "bidirectional"))
    )
    (net (code "268") (name "unconnected-(U$5-DIR_3-PadP$58)") (class "Default")
      (node (ref "U$5") (pin "P$58") (pinfunction "DIR_3_P$58") (pintype "bidirectional"))
    )
    (net (code "269") (name "unconnected-(U$5-DIR_4-PadP$27)") (class "Default")
      (node (ref "U$5") (pin "P$27") (pinfunction "DIR_4_P$27") (pintype "bidirectional"))
    )
    (net (code "270") (name "unconnected-(U$5-DIR_5-PadP$59)") (class "Default")
      (node (ref "U$5") (pin "P$59") (pinfunction "DIR_5_P$59") (pintype "bidirectional"))
    )
    (net (code "271") (name "unconnected-(U$5-DIR_6-PadP$28)") (class "Default")
      (node (ref "U$5") (pin "P$28") (pinfunction "DIR_6_P$28") (pintype "bidirectional"))
    )
    (net (code "272") (name "unconnected-(U$5-ENBL_1-PadP$50)") (class "Default")
      (node (ref "U$5") (pin "P$50") (pinfunction "ENBL_1_P$50") (pintype "bidirectional"))
    )
    (net (code "273") (name "unconnected-(U$5-ENBL_2-PadP$19)") (class "Default")
      (node (ref "U$5") (pin "P$19") (pinfunction "ENBL_2_P$19") (pintype "bidirectional"))
    )
    (net (code "274") (name "unconnected-(U$5-ENBL_3-PadP$51)") (class "Default")
      (node (ref "U$5") (pin "P$51") (pinfunction "ENBL_3_P$51") (pintype "bidirectional"))
    )
    (net (code "275") (name "unconnected-(U$5-ENBL_4-PadP$20)") (class "Default")
      (node (ref "U$5") (pin "P$20") (pinfunction "ENBL_4_P$20") (pintype "bidirectional"))
    )
    (net (code "276") (name "unconnected-(U$5-ENBL_5-PadP$52)") (class "Default")
      (node (ref "U$5") (pin "P$52") (pinfunction "ENBL_5_P$52") (pintype "bidirectional"))
    )
    (net (code "277") (name "unconnected-(U$5-ENBL_6-PadP$21)") (class "Default")
      (node (ref "U$5") (pin "P$21") (pinfunction "ENBL_6_P$21") (pintype "bidirectional"))
    )
    (net (code "278") (name "unconnected-(U$5-LATCH_1-PadP$46)") (class "Default")
      (node (ref "U$5") (pin "P$46") (pinfunction "LATCH_1_P$46") (pintype "bidirectional"))
    )
    (net (code "279") (name "unconnected-(U$5-LATCH_2-PadP$15)") (class "Default")
      (node (ref "U$5") (pin "P$15") (pinfunction "LATCH_2_P$15") (pintype "bidirectional"))
    )
    (net (code "280") (name "unconnected-(U$5-LATCH_3-PadP$47)") (class "Default")
      (node (ref "U$5") (pin "P$47") (pinfunction "LATCH_3_P$47") (pintype "bidirectional"))
    )
    (net (code "281") (name "unconnected-(U$5-LATCH_4-PadP$16)") (class "Default")
      (node (ref "U$5") (pin "P$16") (pinfunction "LATCH_4_P$16") (pintype "bidirectional"))
    )
    (net (code "282") (name "unconnected-(U$5-LATCH_5-PadP$48)") (class "Default")
      (node (ref "U$5") (pin "P$48") (pinfunction "LATCH_5_P$48") (pintype "bidirectional"))
    )
    (net (code "283") (name "unconnected-(U$5-LATCH_6-PadP$17)") (class "Default")
      (node (ref "U$5") (pin "P$17") (pinfunction "LATCH_6_P$17") (pintype "bidirectional"))
    )
    (net (code "284") (name "unconnected-(U$5-OPEN_1-PadP$29)") (class "Default")
      (node (ref "U$5") (pin "P$29") (pinfunction "OPEN_1_P$29") (pintype "bidirectional"))
    )
    (net (code "285") (name "unconnected-(U$5-OPEN_2-PadP$61)") (class "Default")
      (node (ref "U$5") (pin "P$61") (pinfunction "OPEN_2_P$61") (pintype "bidirectional"))
    )
    (net (code "286") (name "unconnected-(U$5-OPEN_3-PadP$30)") (class "Default")
      (node (ref "U$5") (pin "P$30") (pinfunction "OPEN_3_P$30") (pintype "bidirectional"))
    )
    (net (code "287") (name "unconnected-(U$5-OPEN_4-PadP$62)") (class "Default")
      (node (ref "U$5") (pin "P$62") (pinfunction "OPEN_4_P$62") (pintype "bidirectional"))
    )
    (net (code "288") (name "unconnected-(U$5-OPEN_5-PadP$31)") (class "Default")
      (node (ref "U$5") (pin "P$31") (pinfunction "OPEN_5_P$31") (pintype "bidirectional"))
    )
    (net (code "289") (name "unconnected-(U$5-OPEN_6-PadP$63)") (class "Default")
      (node (ref "U$5") (pin "P$63") (pinfunction "OPEN_6_P$63") (pintype "bidirectional"))
    )
    (net (code "290") (name "unconnected-(U$5-OPEN_7-PadP$32)") (class "Default")
      (node (ref "U$5") (pin "P$32") (pinfunction "OPEN_7_P$32") (pintype "bidirectional"))
    )
    (net (code "291") (name "unconnected-(U$5-OPEN_8-PadP$64)") (class "Default")
      (node (ref "U$5") (pin "P$64") (pinfunction "OPEN_8_P$64") (pintype "bidirectional"))
    )
    (net (code "292") (name "unconnected-(U$5-RESET-PadP$18)") (class "Default")
      (node (ref "U$5") (pin "P$18") (pinfunction "RESET_P$18") (pintype "bidirectional"))
    )
    (net (code "293") (name "unconnected-(U$5-STEP_1-PadP$22)") (class "Default")
      (node (ref "U$5") (pin "P$22") (pinfunction "STEP_1_P$22") (pintype "bidirectional"))
    )
    (net (code "294") (name "unconnected-(U$5-STEP_2-PadP$54)") (class "Default")
      (node (ref "U$5") (pin "P$54") (pinfunction "STEP_2_P$54") (pintype "bidirectional"))
    )
    (net (code "295") (name "unconnected-(U$5-STEP_3-PadP$23)") (class "Default")
      (node (ref "U$5") (pin "P$23") (pinfunction "STEP_3_P$23") (pintype "bidirectional"))
    )
    (net (code "296") (name "unconnected-(U$5-STEP_4-PadP$55)") (class "Default")
      (node (ref "U$5") (pin "P$55") (pinfunction "STEP_4_P$55") (pintype "bidirectional"))
    )
    (net (code "297") (name "unconnected-(U$5-STEP_5-PadP$24)") (class "Default")
      (node (ref "U$5") (pin "P$24") (pinfunction "STEP_5_P$24") (pintype "bidirectional"))
    )
    (net (code "298") (name "unconnected-(U$5-STEP_6-PadP$56)") (class "Default")
      (node (ref "U$5") (pin "P$56") (pinfunction "STEP_6_P$56") (pintype "bidirectional"))
    )
    (net (code "299") (name "unconnected-(U$5-SYS_CLK-PadP$45)") (class "Default")
      (node (ref "U$5") (pin "P$45") (pinfunction "SYS_CLK_P$45") (pintype "bidirectional"))
    )
    (net (code "300") (name "unconnected-(U$5-SYS_DAT-PadP$14)") (class "Default")
      (node (ref "U$5") (pin "P$14") (pinfunction "SYS_DAT_P$14") (pintype "bidirectional"))
    )
    (net (code "301") (name "unconnected-(U$6-3V-PadP$12)") (class "Default")
      (node (ref "U$6") (pin "P$12") (pinfunction "3V_P$12") (pintype "bidirectional"))
    )
    (net (code "302") (name "unconnected-(U$6-5V-PadP$44)") (class "Default")
      (node (ref "U$6") (pin "P$44") (pinfunction "5V_P$44") (pintype "bidirectional"))
    )
    (net (code "303") (name "unconnected-(U$6-DIR_1-PadP$57)") (class "Default")
      (node (ref "U$6") (pin "P$57") (pinfunction "DIR_1_P$57") (pintype "bidirectional"))
    )
    (net (code "304") (name "unconnected-(U$6-DIR_2-PadP$26)") (class "Default")
      (node (ref "U$6") (pin "P$26") (pinfunction "DIR_2_P$26") (pintype "bidirectional"))
    )
    (net (code "305") (name "unconnected-(U$6-DIR_3-PadP$58)") (class "Default")
      (node (ref "U$6") (pin "P$58") (pinfunction "DIR_3_P$58") (pintype "bidirectional"))
    )
    (net (code "306") (name "unconnected-(U$6-DIR_4-PadP$27)") (class "Default")
      (node (ref "U$6") (pin "P$27") (pinfunction "DIR_4_P$27") (pintype "bidirectional"))
    )
    (net (code "307") (name "unconnected-(U$6-DIR_5-PadP$59)") (class "Default")
      (node (ref "U$6") (pin "P$59") (pinfunction "DIR_5_P$59") (pintype "bidirectional"))
    )
    (net (code "308") (name "unconnected-(U$6-DIR_6-PadP$28)") (class "Default")
      (node (ref "U$6") (pin "P$28") (pinfunction "DIR_6_P$28") (pintype "bidirectional"))
    )
    (net (code "309") (name "unconnected-(U$6-ENBL_1-PadP$50)") (class "Default")
      (node (ref "U$6") (pin "P$50") (pinfunction "ENBL_1_P$50") (pintype "bidirectional"))
    )
    (net (code "310") (name "unconnected-(U$6-ENBL_2-PadP$19)") (class "Default")
      (node (ref "U$6") (pin "P$19") (pinfunction "ENBL_2_P$19") (pintype "bidirectional"))
    )
    (net (code "311") (name "unconnected-(U$6-ENBL_3-PadP$51)") (class "Default")
      (node (ref "U$6") (pin "P$51") (pinfunction "ENBL_3_P$51") (pintype "bidirectional"))
    )
    (net (code "312") (name "unconnected-(U$6-ENBL_4-PadP$20)") (class "Default")
      (node (ref "U$6") (pin "P$20") (pinfunction "ENBL_4_P$20") (pintype "bidirectional"))
    )
    (net (code "313") (name "unconnected-(U$6-ENBL_5-PadP$52)") (class "Default")
      (node (ref "U$6") (pin "P$52") (pinfunction "ENBL_5_P$52") (pintype "bidirectional"))
    )
    (net (code "314") (name "unconnected-(U$6-ENBL_6-PadP$21)") (class "Default")
      (node (ref "U$6") (pin "P$21") (pinfunction "ENBL_6_P$21") (pintype "bidirectional"))
    )
    (net (code "315") (name "unconnected-(U$6-LATCH_1-PadP$46)") (class "Default")
      (node (ref "U$6") (pin "P$46") (pinfunction "LATCH_1_P$46") (pintype "bidirectional"))
    )
    (net (code "316") (name "unconnected-(U$6-LATCH_2-PadP$15)") (class "Default")
      (node (ref "U$6") (pin "P$15") (pinfunction "LATCH_2_P$15") (pintype "bidirectional"))
    )
    (net (code "317") (name "unconnected-(U$6-LATCH_3-PadP$47)") (class "Default")
      (node (ref "U$6") (pin "P$47") (pinfunction "LATCH_3_P$47") (pintype "bidirectional"))
    )
    (net (code "318") (name "unconnected-(U$6-LATCH_4-PadP$16)") (class "Default")
      (node (ref "U$6") (pin "P$16") (pinfunction "LATCH_4_P$16") (pintype "bidirectional"))
    )
    (net (code "319") (name "unconnected-(U$6-LATCH_5-PadP$48)") (class "Default")
      (node (ref "U$6") (pin "P$48") (pinfunction "LATCH_5_P$48") (pintype "bidirectional"))
    )
    (net (code "320") (name "unconnected-(U$6-LATCH_6-PadP$17)") (class "Default")
      (node (ref "U$6") (pin "P$17") (pinfunction "LATCH_6_P$17") (pintype "bidirectional"))
    )
    (net (code "321") (name "unconnected-(U$6-OPEN_1-PadP$29)") (class "Default")
      (node (ref "U$6") (pin "P$29") (pinfunction "OPEN_1_P$29") (pintype "bidirectional"))
    )
    (net (code "322") (name "unconnected-(U$6-OPEN_2-PadP$61)") (class "Default")
      (node (ref "U$6") (pin "P$61") (pinfunction "OPEN_2_P$61") (pintype "bidirectional"))
    )
    (net (code "323") (name "unconnected-(U$6-OPEN_3-PadP$30)") (class "Default")
      (node (ref "U$6") (pin "P$30") (pinfunction "OPEN_3_P$30") (pintype "bidirectional"))
    )
    (net (code "324") (name "unconnected-(U$6-OPEN_4-PadP$62)") (class "Default")
      (node (ref "U$6") (pin "P$62") (pinfunction "OPEN_4_P$62") (pintype "bidirectional"))
    )
    (net (code "325") (name "unconnected-(U$6-OPEN_5-PadP$31)") (class "Default")
      (node (ref "U$6") (pin "P$31") (pinfunction "OPEN_5_P$31") (pintype "bidirectional"))
    )
    (net (code "326") (name "unconnected-(U$6-OPEN_6-PadP$63)") (class "Default")
      (node (ref "U$6") (pin "P$63") (pinfunction "OPEN_6_P$63") (pintype "bidirectional"))
    )
    (net (code "327") (name "unconnected-(U$6-OPEN_7-PadP$32)") (class "Default")
      (node (ref "U$6") (pin "P$32") (pinfunction "OPEN_7_P$32") (pintype "bidirectional"))
    )
    (net (code "328") (name "unconnected-(U$6-OPEN_8-PadP$64)") (class "Default")
      (node (ref "U$6") (pin "P$64") (pinfunction "OPEN_8_P$64") (pintype "bidirectional"))
    )
    (net (code "329") (name "unconnected-(U$6-RESET-PadP$18)") (class "Default")
      (node (ref "U$6") (pin "P$18") (pinfunction "RESET_P$18") (pintype "bidirectional"))
    )
    (net (code "330") (name "unconnected-(U$6-STEP_1-PadP$22)") (class "Default")
      (node (ref "U$6") (pin "P$22") (pinfunction "STEP_1_P$22") (pintype "bidirectional"))
    )
    (net (code "331") (name "unconnected-(U$6-STEP_2-PadP$54)") (class "Default")
      (node (ref "U$6") (pin "P$54") (pinfunction "STEP_2_P$54") (pintype "bidirectional"))
    )
    (net (code "332") (name "unconnected-(U$6-STEP_3-PadP$23)") (class "Default")
      (node (ref "U$6") (pin "P$23") (pinfunction "STEP_3_P$23") (pintype "bidirectional"))
    )
    (net (code "333") (name "unconnected-(U$6-STEP_4-PadP$55)") (class "Default")
      (node (ref "U$6") (pin "P$55") (pinfunction "STEP_4_P$55") (pintype "bidirectional"))
    )
    (net (code "334") (name "unconnected-(U$6-STEP_5-PadP$24)") (class "Default")
      (node (ref "U$6") (pin "P$24") (pinfunction "STEP_5_P$24") (pintype "bidirectional"))
    )
    (net (code "335") (name "unconnected-(U$6-STEP_6-PadP$56)") (class "Default")
      (node (ref "U$6") (pin "P$56") (pinfunction "STEP_6_P$56") (pintype "bidirectional"))
    )
    (net (code "336") (name "unconnected-(U$6-SYS_CLK-PadP$45)") (class "Default")
      (node (ref "U$6") (pin "P$45") (pinfunction "SYS_CLK_P$45") (pintype "bidirectional"))
    )
    (net (code "337") (name "unconnected-(U$6-SYS_DAT-PadP$14)") (class "Default")
      (node (ref "U$6") (pin "P$14") (pinfunction "SYS_DAT_P$14") (pintype "bidirectional"))
    )
    (net (code "338") (name "unconnected-(U$7-3V-PadP$12)") (class "Default")
      (node (ref "U$7") (pin "P$12") (pinfunction "3V_P$12") (pintype "bidirectional"))
    )
    (net (code "339") (name "unconnected-(U$7-5V-PadP$44)") (class "Default")
      (node (ref "U$7") (pin "P$44") (pinfunction "5V_P$44") (pintype "bidirectional"))
    )
    (net (code "340") (name "unconnected-(U$7-DIR_1-PadP$57)") (class "Default")
      (node (ref "U$7") (pin "P$57") (pinfunction "DIR_1_P$57") (pintype "bidirectional"))
    )
    (net (code "341") (name "unconnected-(U$7-DIR_2-PadP$26)") (class "Default")
      (node (ref "U$7") (pin "P$26") (pinfunction "DIR_2_P$26") (pintype "bidirectional"))
    )
    (net (code "342") (name "unconnected-(U$7-DIR_3-PadP$58)") (class "Default")
      (node (ref "U$7") (pin "P$58") (pinfunction "DIR_3_P$58") (pintype "bidirectional"))
    )
    (net (code "343") (name "unconnected-(U$7-DIR_4-PadP$27)") (class "Default")
      (node (ref "U$7") (pin "P$27") (pinfunction "DIR_4_P$27") (pintype "bidirectional"))
    )
    (net (code "344") (name "unconnected-(U$7-DIR_5-PadP$59)") (class "Default")
      (node (ref "U$7") (pin "P$59") (pinfunction "DIR_5_P$59") (pintype "bidirectional"))
    )
    (net (code "345") (name "unconnected-(U$7-DIR_6-PadP$28)") (class "Default")
      (node (ref "U$7") (pin "P$28") (pinfunction "DIR_6_P$28") (pintype "bidirectional"))
    )
    (net (code "346") (name "unconnected-(U$7-ENBL_1-PadP$50)") (class "Default")
      (node (ref "U$7") (pin "P$50") (pinfunction "ENBL_1_P$50") (pintype "bidirectional"))
    )
    (net (code "347") (name "unconnected-(U$7-ENBL_2-PadP$19)") (class "Default")
      (node (ref "U$7") (pin "P$19") (pinfunction "ENBL_2_P$19") (pintype "bidirectional"))
    )
    (net (code "348") (name "unconnected-(U$7-ENBL_3-PadP$51)") (class "Default")
      (node (ref "U$7") (pin "P$51") (pinfunction "ENBL_3_P$51") (pintype "bidirectional"))
    )
    (net (code "349") (name "unconnected-(U$7-ENBL_4-PadP$20)") (class "Default")
      (node (ref "U$7") (pin "P$20") (pinfunction "ENBL_4_P$20") (pintype "bidirectional"))
    )
    (net (code "350") (name "unconnected-(U$7-ENBL_5-PadP$52)") (class "Default")
      (node (ref "U$7") (pin "P$52") (pinfunction "ENBL_5_P$52") (pintype "bidirectional"))
    )
    (net (code "351") (name "unconnected-(U$7-ENBL_6-PadP$21)") (class "Default")
      (node (ref "U$7") (pin "P$21") (pinfunction "ENBL_6_P$21") (pintype "bidirectional"))
    )
    (net (code "352") (name "unconnected-(U$7-LATCH_1-PadP$46)") (class "Default")
      (node (ref "U$7") (pin "P$46") (pinfunction "LATCH_1_P$46") (pintype "bidirectional"))
    )
    (net (code "353") (name "unconnected-(U$7-LATCH_2-PadP$15)") (class "Default")
      (node (ref "U$7") (pin "P$15") (pinfunction "LATCH_2_P$15") (pintype "bidirectional"))
    )
    (net (code "354") (name "unconnected-(U$7-LATCH_3-PadP$47)") (class "Default")
      (node (ref "U$7") (pin "P$47") (pinfunction "LATCH_3_P$47") (pintype "bidirectional"))
    )
    (net (code "355") (name "unconnected-(U$7-LATCH_4-PadP$16)") (class "Default")
      (node (ref "U$7") (pin "P$16") (pinfunction "LATCH_4_P$16") (pintype "bidirectional"))
    )
    (net (code "356") (name "unconnected-(U$7-LATCH_5-PadP$48)") (class "Default")
      (node (ref "U$7") (pin "P$48") (pinfunction "LATCH_5_P$48") (pintype "bidirectional"))
    )
    (net (code "357") (name "unconnected-(U$7-LATCH_6-PadP$17)") (class "Default")
      (node (ref "U$7") (pin "P$17") (pinfunction "LATCH_6_P$17") (pintype "bidirectional"))
    )
    (net (code "358") (name "unconnected-(U$7-OPEN_1-PadP$29)") (class "Default")
      (node (ref "U$7") (pin "P$29") (pinfunction "OPEN_1_P$29") (pintype "bidirectional"))
    )
    (net (code "359") (name "unconnected-(U$7-OPEN_2-PadP$61)") (class "Default")
      (node (ref "U$7") (pin "P$61") (pinfunction "OPEN_2_P$61") (pintype "bidirectional"))
    )
    (net (code "360") (name "unconnected-(U$7-OPEN_3-PadP$30)") (class "Default")
      (node (ref "U$7") (pin "P$30") (pinfunction "OPEN_3_P$30") (pintype "bidirectional"))
    )
    (net (code "361") (name "unconnected-(U$7-OPEN_4-PadP$62)") (class "Default")
      (node (ref "U$7") (pin "P$62") (pinfunction "OPEN_4_P$62") (pintype "bidirectional"))
    )
    (net (code "362") (name "unconnected-(U$7-OPEN_5-PadP$31)") (class "Default")
      (node (ref "U$7") (pin "P$31") (pinfunction "OPEN_5_P$31") (pintype "bidirectional"))
    )
    (net (code "363") (name "unconnected-(U$7-OPEN_6-PadP$63)") (class "Default")
      (node (ref "U$7") (pin "P$63") (pinfunction "OPEN_6_P$63") (pintype "bidirectional"))
    )
    (net (code "364") (name "unconnected-(U$7-OPEN_7-PadP$32)") (class "Default")
      (node (ref "U$7") (pin "P$32") (pinfunction "OPEN_7_P$32") (pintype "bidirectional"))
    )
    (net (code "365") (name "unconnected-(U$7-OPEN_8-PadP$64)") (class "Default")
      (node (ref "U$7") (pin "P$64") (pinfunction "OPEN_8_P$64") (pintype "bidirectional"))
    )
    (net (code "366") (name "unconnected-(U$7-RESET-PadP$18)") (class "Default")
      (node (ref "U$7") (pin "P$18") (pinfunction "RESET_P$18") (pintype "bidirectional"))
    )
    (net (code "367") (name "unconnected-(U$7-STEP_1-PadP$22)") (class "Default")
      (node (ref "U$7") (pin "P$22") (pinfunction "STEP_1_P$22") (pintype "bidirectional"))
    )
    (net (code "368") (name "unconnected-(U$7-STEP_2-PadP$54)") (class "Default")
      (node (ref "U$7") (pin "P$54") (pinfunction "STEP_2_P$54") (pintype "bidirectional"))
    )
    (net (code "369") (name "unconnected-(U$7-STEP_3-PadP$23)") (class "Default")
      (node (ref "U$7") (pin "P$23") (pinfunction "STEP_3_P$23") (pintype "bidirectional"))
    )
    (net (code "370") (name "unconnected-(U$7-STEP_4-PadP$55)") (class "Default")
      (node (ref "U$7") (pin "P$55") (pinfunction "STEP_4_P$55") (pintype "bidirectional"))
    )
    (net (code "371") (name "unconnected-(U$7-STEP_5-PadP$24)") (class "Default")
      (node (ref "U$7") (pin "P$24") (pinfunction "STEP_5_P$24") (pintype "bidirectional"))
    )
    (net (code "372") (name "unconnected-(U$7-STEP_6-PadP$56)") (class "Default")
      (node (ref "U$7") (pin "P$56") (pinfunction "STEP_6_P$56") (pintype "bidirectional"))
    )
    (net (code "373") (name "unconnected-(U$7-SYS_CLK-PadP$45)") (class "Default")
      (node (ref "U$7") (pin "P$45") (pinfunction "SYS_CLK_P$45") (pintype "bidirectional"))
    )
    (net (code "374") (name "unconnected-(U$7-SYS_DAT-PadP$14)") (class "Default")
      (node (ref "U$7") (pin "P$14") (pinfunction "SYS_DAT_P$14") (pintype "bidirectional"))
    )
    (net (code "375") (name "unconnected-(U$22-P$2-PadP$34)") (class "Default")
      (node (ref "U$22") (pin "P$34") (pinfunction "P$2_P$34") (pintype "bidirectional"))
    )
    (net (code "376") (name "unconnected-(U$22-PadP$1)") (class "Default")
      (node (ref "U$22") (pin "P$1") (pinfunction "P$1_P$1") (pintype "bidirectional"))
    )
    (net (code "377") (name "unconnected-(U$23-P$2-PadP$34)") (class "Default")
      (node (ref "U$23") (pin "P$34") (pinfunction "P$2_P$34") (pintype "bidirectional"))
    )
    (net (code "378") (name "unconnected-(U$23-PadP$1)") (class "Default")
      (node (ref "U$23") (pin "P$1") (pinfunction "P$1_P$1") (pintype "bidirectional"))
    )
    (net (code "379") (name "unconnected-(U$24-P$2-PadP$34)") (class "Default")
      (node (ref "U$24") (pin "P$34") (pinfunction "P$2_P$34") (pintype "bidirectional"))
    )
    (net (code "380") (name "unconnected-(U$24-PadP$1)") (class "Default")
      (node (ref "U$24") (pin "P$1") (pinfunction "P$1_P$1") (pintype "bidirectional"))
    )
    (net (code "381") (name "unconnected-(U$25-P$2-PadP$34)") (class "Default")
      (node (ref "U$25") (pin "P$34") (pinfunction "P$2_P$34") (pintype "bidirectional"))
    )
    (net (code "382") (name "unconnected-(U$25-PadP$1)") (class "Default")
      (node (ref "U$25") (pin "P$1") (pinfunction "P$1_P$1") (pintype "bidirectional"))
    )
    (net (code "383") (name "unconnected-(U$26-P$2-PadP$34)") (class "Default")
      (node (ref "U$26") (pin "P$34") (pinfunction "P$2_P$34") (pintype "bidirectional"))
    )
    (net (code "384") (name "unconnected-(U$26-PadP$1)") (class "Default")
      (node (ref "U$26") (pin "P$1") (pinfunction "P$1_P$1") (pintype "bidirectional"))
    )
    (net (code "385") (name "unconnected-(U$27-P$2-PadP$34)") (class "Default")
      (node (ref "U$27") (pin "P$34") (pinfunction "P$2_P$34") (pintype "bidirectional"))
    )
    (net (code "386") (name "unconnected-(U$27-PadP$1)") (class "Default")
      (node (ref "U$27") (pin "P$1") (pinfunction "P$1_P$1") (pintype "bidirectional"))
    )
    (net (code "387") (name "unconnected-(U$35-PadP$1)") (class "Default")
      (node (ref "U$35") (pin "P$1") (pinfunction "P$1_P$1") (pintype "bidirectional"))
    )
    (net (code "388") (name "unconnected-(U$35-PadP$3)") (class "Default")
      (node (ref "U$35") (pin "P$3") (pinfunction "P$3_P$3") (pintype "bidirectional"))
    )
    (net (code "389") (name "unconnected-(U$36-PadP$1)") (class "Default")
      (node (ref "U$36") (pin "P$1") (pinfunction "P$1_P$1") (pintype "bidirectional"))
    )
    (net (code "390") (name "unconnected-(U$36-PadP$3)") (class "Default")
      (node (ref "U$36") (pin "P$3") (pinfunction "P$3_P$3") (pintype "bidirectional"))
    )
    (net (code "391") (name "unconnected-(U$37-PadP$1)") (class "Default")
      (node (ref "U$37") (pin "P$1") (pinfunction "P$1_P$1") (pintype "bidirectional"))
    )
    (net (code "392") (name "unconnected-(U$37-PadP$3)") (class "Default")
      (node (ref "U$37") (pin "P$3") (pinfunction "P$3_P$3") (pintype "bidirectional"))
    )
    (net (code "393") (name "unconnected-(U$41-P$2-PadP$5)") (class "Default")
      (node (ref "U$41") (pin "P$5") (pinfunction "P$2_P$5") (pintype "bidirectional"))
    )
    (net (code "394") (name "unconnected-(U$42-PadP$1)") (class "Default")
      (node (ref "U$42") (pin "P$1") (pinfunction "P$1_P$1") (pintype "bidirectional"))
    )
    (net (code "395") (name "unconnected-(U$42-PadP$3)") (class "Default")
      (node (ref "U$42") (pin "P$3") (pinfunction "P$3_P$3") (pintype "bidirectional"))
    )
  )
)
